# TRS-80.net
KiCad netlist of a schematic drawn in EAGLE
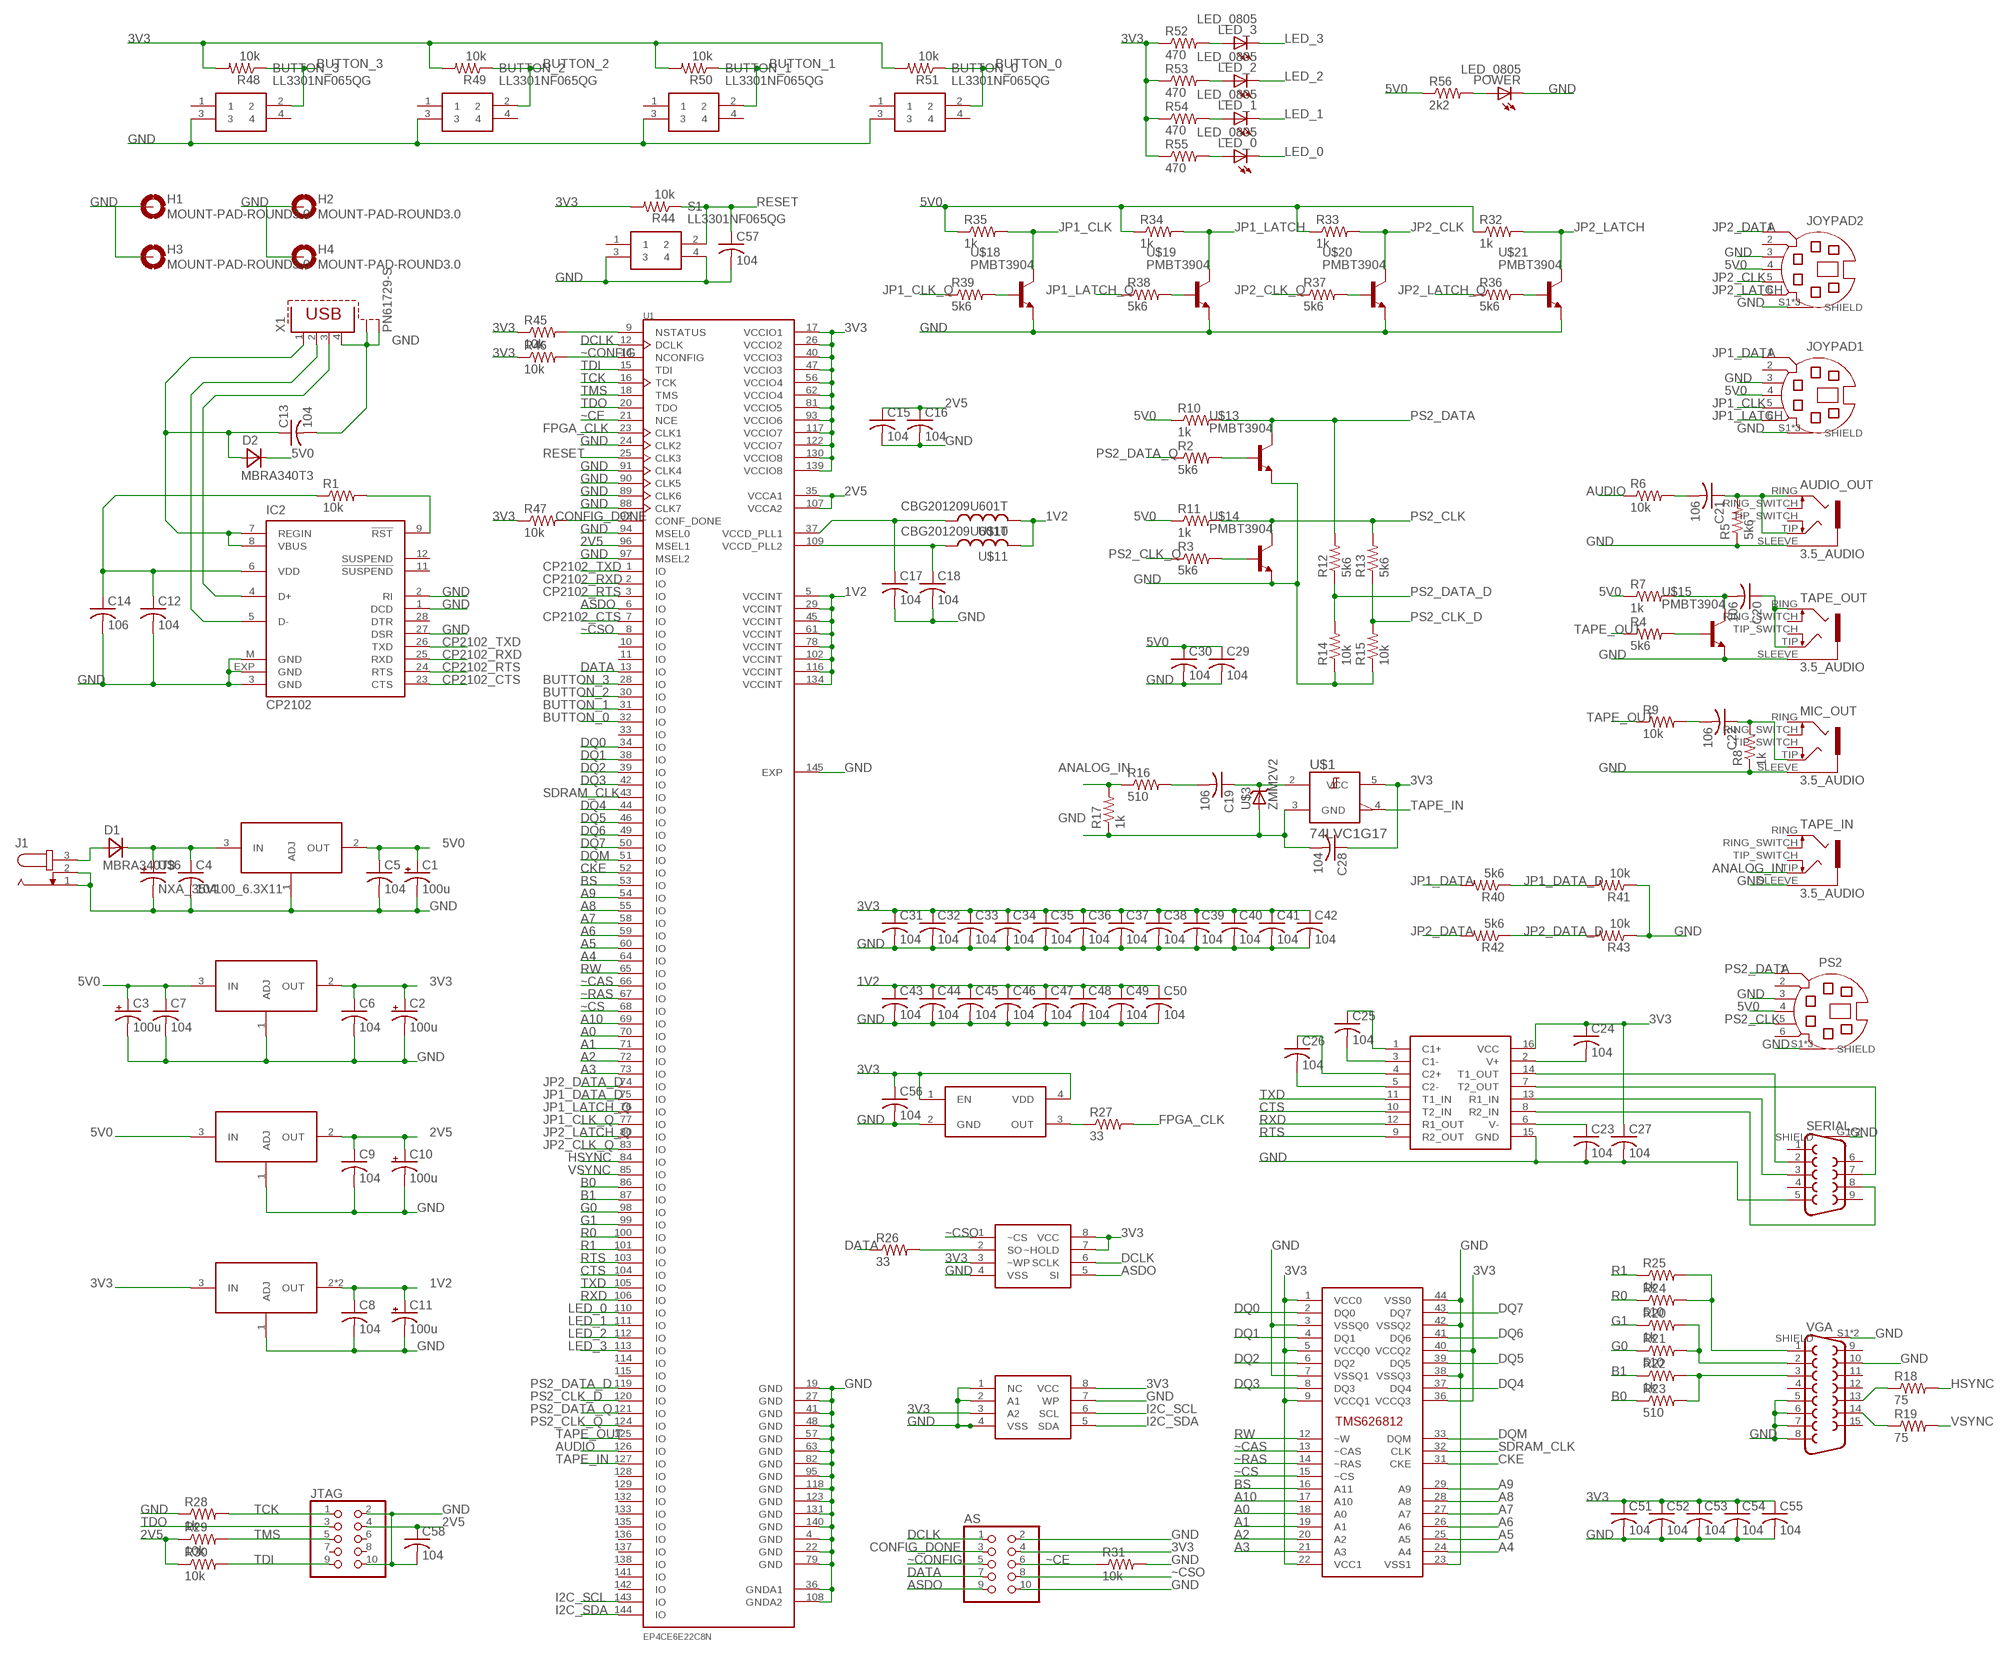
[diagram p0: schematic, sheet 1]

(export (version "E")
  (design (tool "Eeschema 10.0.6"))
  (components
    (comp (ref "AS")
      (value "PINHD-2X5")
      (footprint "eagle-import:2X05")
      (libsource (lib "eagle-import") (part "PINHD-2X5"))
    )
    (comp (ref "AUDIO_OUT")
      (value "3.5_AUDIO")
      (footprint "eagle-import:3.5_AUDIO")
      (libsource (lib "eagle-import") (part "3.5_AUDIO"))
    )
    (comp (ref "BUTTON_0")
      (value "LL3301NF065QG")
      (footprint "eagle-import:LL3301NF065QG")
      (fields (field (name "MOUSER_PART_NUMBER") "612-LL3301NF065QG"))
      (libsource (lib "eagle-import") (part "LL3301NF065QG"))
    )
    (comp (ref "BUTTON_1")
      (value "LL3301NF065QG")
      (footprint "eagle-import:LL3301NF065QG")
      (fields (field (name "MOUSER_PART_NUMBER") "612-LL3301NF065QG"))
      (libsource (lib "eagle-import") (part "LL3301NF065QG"))
    )
    (comp (ref "BUTTON_2")
      (value "LL3301NF065QG")
      (footprint "eagle-import:LL3301NF065QG")
      (fields (field (name "MOUSER_PART_NUMBER") "612-LL3301NF065QG"))
      (libsource (lib "eagle-import") (part "LL3301NF065QG"))
    )
    (comp (ref "BUTTON_3")
      (value "LL3301NF065QG")
      (footprint "eagle-import:LL3301NF065QG")
      (fields (field (name "MOUSER_PART_NUMBER") "612-LL3301NF065QG"))
      (libsource (lib "eagle-import") (part "LL3301NF065QG"))
    )
    (comp (ref "C1")
      (value "100u")
      (footprint "eagle-import:UD-6,3X5,8_NICHICON")
      (libsource (lib "eagle-import") (part "CPOL-USUD-6,3X5,8"))
    )
    (comp (ref "C2")
      (value "100u")
      (footprint "eagle-import:UD-6,3X5,8_NICHICON")
      (libsource (lib "eagle-import") (part "CPOL-USUD-6,3X5,8"))
    )
    (comp (ref "C3")
      (value "100u")
      (footprint "eagle-import:UD-6,3X5,8_NICHICON")
      (libsource (lib "eagle-import") (part "CPOL-USUD-6,3X5,8"))
    )
    (comp (ref "C4")
      (value "104")
      (footprint "eagle-import:C0805")
      (libsource (lib "eagle-import") (part "C-USC0805"))
    )
    (comp (ref "C5")
      (value "104")
      (footprint "eagle-import:C0805")
      (libsource (lib "eagle-import") (part "C-USC0805"))
    )
    (comp (ref "C6")
      (value "104")
      (footprint "eagle-import:C0805")
      (libsource (lib "eagle-import") (part "C-USC0805"))
    )
    (comp (ref "C7")
      (value "104")
      (footprint "eagle-import:C0805")
      (libsource (lib "eagle-import") (part "C-USC0805"))
    )
    (comp (ref "C8")
      (value "104")
      (footprint "eagle-import:C0805")
      (libsource (lib "eagle-import") (part "C-USC0805"))
    )
    (comp (ref "C9")
      (value "104")
      (footprint "eagle-import:C0805")
      (libsource (lib "eagle-import") (part "C-USC0805"))
    )
    (comp (ref "C10")
      (value "100u")
      (footprint "eagle-import:UD-6,3X5,8_NICHICON")
      (libsource (lib "eagle-import") (part "CPOL-USUD-6,3X5,8"))
    )
    (comp (ref "C11")
      (value "100u")
      (footprint "eagle-import:UD-6,3X5,8_NICHICON")
      (libsource (lib "eagle-import") (part "CPOL-USUD-6,3X5,8"))
    )
    (comp (ref "C12")
      (value "104")
      (footprint "eagle-import:C0805")
      (libsource (lib "eagle-import") (part "C-USC0805"))
    )
    (comp (ref "C13")
      (value "104")
      (footprint "eagle-import:C0805")
      (libsource (lib "eagle-import") (part "C-USC0805"))
    )
    (comp (ref "C14")
      (value "106")
      (footprint "eagle-import:C1206")
      (libsource (lib "eagle-import") (part "C-USC1206"))
    )
    (comp (ref "C15")
      (value "104")
      (footprint "eagle-import:C0805")
      (libsource (lib "eagle-import") (part "C-USC0805"))
    )
    (comp (ref "C16")
      (value "104")
      (footprint "eagle-import:C0805")
      (libsource (lib "eagle-import") (part "C-USC0805"))
    )
    (comp (ref "C17")
      (value "104")
      (footprint "eagle-import:C0805")
      (libsource (lib "eagle-import") (part "C-USC0805"))
    )
    (comp (ref "C18")
      (value "104")
      (footprint "eagle-import:C0805")
      (libsource (lib "eagle-import") (part "C-USC0805"))
    )
    (comp (ref "C19")
      (value "106")
      (footprint "eagle-import:C1206")
      (libsource (lib "eagle-import") (part "C-USC1206"))
    )
    (comp (ref "C20")
      (value "106")
      (footprint "eagle-import:C1206")
      (libsource (lib "eagle-import") (part "C-USC1206"))
    )
    (comp (ref "C21")
      (value "106")
      (footprint "eagle-import:C1206")
      (libsource (lib "eagle-import") (part "C-USC1206"))
    )
    (comp (ref "C22")
      (value "106")
      (footprint "eagle-import:C1206")
      (libsource (lib "eagle-import") (part "C-USC1206"))
    )
    (comp (ref "C23")
      (value "104")
      (footprint "eagle-import:C0805")
      (libsource (lib "eagle-import") (part "C-USC0805"))
    )
    (comp (ref "C24")
      (value "104")
      (footprint "eagle-import:C0805")
      (libsource (lib "eagle-import") (part "C-USC0805"))
    )
    (comp (ref "C25")
      (value "104")
      (footprint "eagle-import:C0805")
      (libsource (lib "eagle-import") (part "C-USC0805"))
    )
    (comp (ref "C26")
      (value "104")
      (footprint "eagle-import:C0805")
      (libsource (lib "eagle-import") (part "C-USC0805"))
    )
    (comp (ref "C27")
      (value "104")
      (footprint "eagle-import:C0805")
      (libsource (lib "eagle-import") (part "C-USC0805"))
    )
    (comp (ref "C28")
      (value "104")
      (footprint "eagle-import:C0805")
      (libsource (lib "eagle-import") (part "C-USC0805"))
    )
    (comp (ref "C29")
      (value "104")
      (footprint "eagle-import:C0805")
      (libsource (lib "eagle-import") (part "C-USC0805"))
    )
    (comp (ref "C30")
      (value "104")
      (footprint "eagle-import:C0805")
      (libsource (lib "eagle-import") (part "C-USC0805"))
    )
    (comp (ref "C31")
      (value "104")
      (footprint "eagle-import:C0805")
      (libsource (lib "eagle-import") (part "C-USC0805"))
    )
    (comp (ref "C32")
      (value "104")
      (footprint "eagle-import:C0805")
      (libsource (lib "eagle-import") (part "C-USC0805"))
    )
    (comp (ref "C33")
      (value "104")
      (footprint "eagle-import:C0805")
      (libsource (lib "eagle-import") (part "C-USC0805"))
    )
    (comp (ref "C34")
      (value "104")
      (footprint "eagle-import:C0805")
      (libsource (lib "eagle-import") (part "C-USC0805"))
    )
    (comp (ref "C35")
      (value "104")
      (footprint "eagle-import:C0805")
      (libsource (lib "eagle-import") (part "C-USC0805"))
    )
    (comp (ref "C36")
      (value "104")
      (footprint "eagle-import:C0805")
      (libsource (lib "eagle-import") (part "C-USC0805"))
    )
    (comp (ref "C37")
      (value "104")
      (footprint "eagle-import:C0805")
      (libsource (lib "eagle-import") (part "C-USC0805"))
    )
    (comp (ref "C38")
      (value "104")
      (footprint "eagle-import:C0805")
      (libsource (lib "eagle-import") (part "C-USC0805"))
    )
    (comp (ref "C39")
      (value "104")
      (footprint "eagle-import:C0805")
      (libsource (lib "eagle-import") (part "C-USC0805"))
    )
    (comp (ref "C40")
      (value "104")
      (footprint "eagle-import:C0805")
      (libsource (lib "eagle-import") (part "C-USC0805"))
    )
    (comp (ref "C41")
      (value "104")
      (footprint "eagle-import:C0805")
      (libsource (lib "eagle-import") (part "C-USC0805"))
    )
    (comp (ref "C42")
      (value "104")
      (footprint "eagle-import:C0805")
      (libsource (lib "eagle-import") (part "C-USC0805"))
    )
    (comp (ref "C43")
      (value "104")
      (footprint "eagle-import:C0805")
      (libsource (lib "eagle-import") (part "C-USC0805"))
    )
    (comp (ref "C44")
      (value "104")
      (footprint "eagle-import:C0805")
      (libsource (lib "eagle-import") (part "C-USC0805"))
    )
    (comp (ref "C45")
      (value "104")
      (footprint "eagle-import:C0805")
      (libsource (lib "eagle-import") (part "C-USC0805"))
    )
    (comp (ref "C46")
      (value "104")
      (footprint "eagle-import:C0805")
      (libsource (lib "eagle-import") (part "C-USC0805"))
    )
    (comp (ref "C47")
      (value "104")
      (footprint "eagle-import:C0805")
      (libsource (lib "eagle-import") (part "C-USC0805"))
    )
    (comp (ref "C48")
      (value "104")
      (footprint "eagle-import:C0805")
      (libsource (lib "eagle-import") (part "C-USC0805"))
    )
    (comp (ref "C49")
      (value "104")
      (footprint "eagle-import:C0805")
      (libsource (lib "eagle-import") (part "C-USC0805"))
    )
    (comp (ref "C50")
      (value "104")
      (footprint "eagle-import:C0805")
      (libsource (lib "eagle-import") (part "C-USC0805"))
    )
    (comp (ref "C51")
      (value "104")
      (footprint "eagle-import:C0805")
      (libsource (lib "eagle-import") (part "C-USC0805"))
    )
    (comp (ref "C52")
      (value "104")
      (footprint "eagle-import:C0805")
      (libsource (lib "eagle-import") (part "C-USC0805"))
    )
    (comp (ref "C53")
      (value "104")
      (footprint "eagle-import:C0805")
      (libsource (lib "eagle-import") (part "C-USC0805"))
    )
    (comp (ref "C54")
      (value "104")
      (footprint "eagle-import:C0805")
      (libsource (lib "eagle-import") (part "C-USC0805"))
    )
    (comp (ref "C55")
      (value "104")
      (footprint "eagle-import:C0805")
      (libsource (lib "eagle-import") (part "C-USC0805"))
    )
    (comp (ref "C56")
      (value "104")
      (footprint "eagle-import:C0805")
      (libsource (lib "eagle-import") (part "C-USC0805"))
    )
    (comp (ref "C57")
      (value "104")
      (footprint "eagle-import:C0805")
      (libsource (lib "eagle-import") (part "C-USC0805"))
    )
    (comp (ref "C58")
      (value "104")
      (footprint "eagle-import:C0805")
      (libsource (lib "eagle-import") (part "C-USC0805"))
    )
    (comp (ref "D1")
      (value "MBRA340T3")
      (footprint "eagle-import:SMA")
      (libsource (lib "eagle-import") (part "MBRA340T3"))
    )
    (comp (ref "D2")
      (value "MBRA340T3")
      (footprint "eagle-import:SMA")
      (libsource (lib "eagle-import") (part "MBRA340T3"))
    )
    (comp (ref "H1")
      (value "MOUNT-PAD-ROUND3.0")
      (footprint "eagle-import:3,0-PAD")
      (libsource (lib "eagle-import") (part "MOUNT-PAD-ROUND3.0"))
    )
    (comp (ref "H2")
      (value "MOUNT-PAD-ROUND3.0")
      (footprint "eagle-import:3,0-PAD")
      (libsource (lib "eagle-import") (part "MOUNT-PAD-ROUND3.0"))
    )
    (comp (ref "H3")
      (value "MOUNT-PAD-ROUND3.0")
      (footprint "eagle-import:3,0-PAD")
      (libsource (lib "eagle-import") (part "MOUNT-PAD-ROUND3.0"))
    )
    (comp (ref "H4")
      (value "MOUNT-PAD-ROUND3.0")
      (footprint "eagle-import:3,0-PAD")
      (libsource (lib "eagle-import") (part "MOUNT-PAD-ROUND3.0"))
    )
    (comp (ref "IC2")
      (value "CP2102")
      (footprint "eagle-import:MLP28")
      (fields (field (name "MF") "FARNELL") (field (name "MPN") "CP2102-GM"))
      (libsource (lib "eagle-import") (part "CP2102"))
    )
    (comp (ref "J1")
      (value "JACK-PLUG1")
      (footprint "eagle-import:SPC4078")
      (libsource (lib "eagle-import") (part "JACK-PLUG1"))
    )
    (comp (ref "JOYPAD1")
      (value "MD06SS")
      (footprint "eagle-import:MDIN06SS")
      (libsource (lib "eagle-import") (part "MD06SS"))
    )
    (comp (ref "JOYPAD2")
      (value "MD06SS")
      (footprint "eagle-import:MDIN06SS")
      (libsource (lib "eagle-import") (part "MD06SS"))
    )
    (comp (ref "JTAG")
      (value "PINHD-2X5")
      (footprint "eagle-import:2X05")
      (libsource (lib "eagle-import") (part "PINHD-2X5"))
    )
    (comp (ref "LED_0")
      (value "LED_0805")
      (footprint "eagle-import:CHIP-LED0805")
      (libsource (lib "eagle-import") (part "LED_0805"))
    )
    (comp (ref "LED_1")
      (value "LED_0805")
      (footprint "eagle-import:CHIP-LED0805")
      (libsource (lib "eagle-import") (part "LED_0805"))
    )
    (comp (ref "LED_2")
      (value "LED_0805")
      (footprint "eagle-import:CHIP-LED0805")
      (libsource (lib "eagle-import") (part "LED_0805"))
    )
    (comp (ref "LED_3")
      (value "LED_0805")
      (footprint "eagle-import:CHIP-LED0805")
      (libsource (lib "eagle-import") (part "LED_0805"))
    )
    (comp (ref "MIC_OUT")
      (value "3.5_AUDIO")
      (footprint "eagle-import:3.5_AUDIO")
      (libsource (lib "eagle-import") (part "3.5_AUDIO"))
    )
    (comp (ref "POWER")
      (value "LED_0805")
      (footprint "eagle-import:CHIP-LED0805")
      (libsource (lib "eagle-import") (part "LED_0805"))
    )
    (comp (ref "PS2")
      (value "MD06SS")
      (footprint "eagle-import:MDIN06SS")
      (libsource (lib "eagle-import") (part "MD06SS"))
    )
    (comp (ref "R1")
      (value "10k")
      (footprint "eagle-import:R0805")
      (libsource (lib "eagle-import") (part "R-US_R0805"))
    )
    (comp (ref "R2")
      (value "5k6")
      (footprint "eagle-import:R0805")
      (libsource (lib "eagle-import") (part "R-US_R0805"))
    )
    (comp (ref "R3")
      (value "5k6")
      (footprint "eagle-import:R0805")
      (libsource (lib "eagle-import") (part "R-US_R0805"))
    )
    (comp (ref "R4")
      (value "5k6")
      (footprint "eagle-import:R0805")
      (libsource (lib "eagle-import") (part "R-US_R0805"))
    )
    (comp (ref "R5")
      (value "5k6")
      (footprint "eagle-import:R0805")
      (libsource (lib "eagle-import") (part "R-US_R0805"))
    )
    (comp (ref "R6")
      (value "10k")
      (footprint "eagle-import:R0805")
      (libsource (lib "eagle-import") (part "R-US_R0805"))
    )
    (comp (ref "R7")
      (value "1k")
      (footprint "eagle-import:R0805")
      (libsource (lib "eagle-import") (part "R-US_R0805"))
    )
    (comp (ref "R8")
      (value "1k")
      (footprint "eagle-import:R0805")
      (libsource (lib "eagle-import") (part "R-US_R0805"))
    )
    (comp (ref "R9")
      (value "10k")
      (footprint "eagle-import:R0805")
      (libsource (lib "eagle-import") (part "R-US_R0805"))
    )
    (comp (ref "R10")
      (value "1k")
      (footprint "eagle-import:R0805")
      (libsource (lib "eagle-import") (part "R-US_R0805"))
    )
    (comp (ref "R11")
      (value "1k")
      (footprint "eagle-import:R0805")
      (libsource (lib "eagle-import") (part "R-US_R0805"))
    )
    (comp (ref "R12")
      (value "5k6")
      (footprint "eagle-import:R0805")
      (libsource (lib "eagle-import") (part "R-US_R0805"))
    )
    (comp (ref "R13")
      (value "5k6")
      (footprint "eagle-import:R0805")
      (libsource (lib "eagle-import") (part "R-US_R0805"))
    )
    (comp (ref "R14")
      (value "10k")
      (footprint "eagle-import:R0805")
      (libsource (lib "eagle-import") (part "R-US_R0805"))
    )
    (comp (ref "R15")
      (value "10k")
      (footprint "eagle-import:R0805")
      (libsource (lib "eagle-import") (part "R-US_R0805"))
    )
    (comp (ref "R16")
      (value "510")
      (footprint "eagle-import:R0805")
      (libsource (lib "eagle-import") (part "R-US_R0805"))
    )
    (comp (ref "R17")
      (value "1k")
      (footprint "eagle-import:R0805")
      (libsource (lib "eagle-import") (part "R-US_R0805"))
    )
    (comp (ref "R18")
      (value "75")
      (footprint "eagle-import:R0805")
      (libsource (lib "eagle-import") (part "R-US_R0805"))
    )
    (comp (ref "R19")
      (value "75")
      (footprint "eagle-import:R0805")
      (libsource (lib "eagle-import") (part "R-US_R0805"))
    )
    (comp (ref "R20")
      (value "1k")
      (footprint "eagle-import:R0805")
      (libsource (lib "eagle-import") (part "R-US_R0805"))
    )
    (comp (ref "R21")
      (value "510")
      (footprint "eagle-import:R0805")
      (libsource (lib "eagle-import") (part "R-US_R0805"))
    )
    (comp (ref "R22")
      (value "1k")
      (footprint "eagle-import:R0805")
      (libsource (lib "eagle-import") (part "R-US_R0805"))
    )
    (comp (ref "R23")
      (value "510")
      (footprint "eagle-import:R0805")
      (libsource (lib "eagle-import") (part "R-US_R0805"))
    )
    (comp (ref "R24")
      (value "510")
      (footprint "eagle-import:R0805")
      (libsource (lib "eagle-import") (part "R-US_R0805"))
    )
    (comp (ref "R25")
      (value "1k")
      (footprint "eagle-import:R0805")
      (libsource (lib "eagle-import") (part "R-US_R0805"))
    )
    (comp (ref "R26")
      (value "33")
      (footprint "eagle-import:R0805")
      (libsource (lib "eagle-import") (part "R-US_R0805"))
    )
    (comp (ref "R27")
      (value "33")
      (footprint "eagle-import:R0805")
      (libsource (lib "eagle-import") (part "R-US_R0805"))
    )
    (comp (ref "R28")
      (value "1k")
      (footprint "eagle-import:R0805")
      (libsource (lib "eagle-import") (part "R-US_R0805"))
    )
    (comp (ref "R29")
      (value "10k")
      (footprint "eagle-import:R0805")
      (libsource (lib "eagle-import") (part "R-US_R0805"))
    )
    (comp (ref "R30")
      (value "10k")
      (footprint "eagle-import:R0805")
      (libsource (lib "eagle-import") (part "R-US_R0805"))
    )
    (comp (ref "R31")
      (value "10k")
      (footprint "eagle-import:R0805")
      (libsource (lib "eagle-import") (part "R-US_R0805"))
    )
    (comp (ref "R32")
      (value "1k")
      (footprint "eagle-import:R0805")
      (libsource (lib "eagle-import") (part "R-US_R0805"))
    )
    (comp (ref "R33")
      (value "1k")
      (footprint "eagle-import:R0805")
      (libsource (lib "eagle-import") (part "R-US_R0805"))
    )
    (comp (ref "R34")
      (value "1k")
      (footprint "eagle-import:R0805")
      (libsource (lib "eagle-import") (part "R-US_R0805"))
    )
    (comp (ref "R35")
      (value "1k")
      (footprint "eagle-import:R0805")
      (libsource (lib "eagle-import") (part "R-US_R0805"))
    )
    (comp (ref "R36")
      (value "5k6")
      (footprint "eagle-import:R0805")
      (libsource (lib "eagle-import") (part "R-US_R0805"))
    )
    (comp (ref "R37")
      (value "5k6")
      (footprint "eagle-import:R0805")
      (libsource (lib "eagle-import") (part "R-US_R0805"))
    )
    (comp (ref "R38")
      (value "5k6")
      (footprint "eagle-import:R0805")
      (libsource (lib "eagle-import") (part "R-US_R0805"))
    )
    (comp (ref "R39")
      (value "5k6")
      (footprint "eagle-import:R0805")
      (libsource (lib "eagle-import") (part "R-US_R0805"))
    )
    (comp (ref "R40")
      (value "5k6")
      (footprint "eagle-import:R0805")
      (libsource (lib "eagle-import") (part "R-US_R0805"))
    )
    (comp (ref "R41")
      (value "10k")
      (footprint "eagle-import:R0805")
      (libsource (lib "eagle-import") (part "R-US_R0805"))
    )
    (comp (ref "R42")
      (value "5k6")
      (footprint "eagle-import:R0805")
      (libsource (lib "eagle-import") (part "R-US_R0805"))
    )
    (comp (ref "R43")
      (value "10k")
      (footprint "eagle-import:R0805")
      (libsource (lib "eagle-import") (part "R-US_R0805"))
    )
    (comp (ref "R44")
      (value "10k")
      (footprint "eagle-import:R0805")
      (libsource (lib "eagle-import") (part "R-US_R0805"))
    )
    (comp (ref "R45")
      (value "10k")
      (footprint "eagle-import:R0805")
      (libsource (lib "eagle-import") (part "R-US_R0805"))
    )
    (comp (ref "R46")
      (value "10k")
      (footprint "eagle-import:R0805")
      (libsource (lib "eagle-import") (part "R-US_R0805"))
    )
    (comp (ref "R47")
      (value "10k")
      (footprint "eagle-import:R0805")
      (libsource (lib "eagle-import") (part "R-US_R0805"))
    )
    (comp (ref "R48")
      (value "10k")
      (footprint "eagle-import:R0805")
      (libsource (lib "eagle-import") (part "R-US_R0805"))
    )
    (comp (ref "R49")
      (value "10k")
      (footprint "eagle-import:R0805")
      (libsource (lib "eagle-import") (part "R-US_R0805"))
    )
    (comp (ref "R50")
      (value "10k")
      (footprint "eagle-import:R0805")
      (libsource (lib "eagle-import") (part "R-US_R0805"))
    )
    (comp (ref "R51")
      (value "10k")
      (footprint "eagle-import:R0805")
      (libsource (lib "eagle-import") (part "R-US_R0805"))
    )
    (comp (ref "R52")
      (value "470")
      (footprint "eagle-import:R0805")
      (libsource (lib "eagle-import") (part "R-US_R0805"))
    )
    (comp (ref "R53")
      (value "470")
      (footprint "eagle-import:R0805")
      (libsource (lib "eagle-import") (part "R-US_R0805"))
    )
    (comp (ref "R54")
      (value "470")
      (footprint "eagle-import:R0805")
      (libsource (lib "eagle-import") (part "R-US_R0805"))
    )
    (comp (ref "R55")
      (value "470")
      (footprint "eagle-import:R0805")
      (libsource (lib "eagle-import") (part "R-US_R0805"))
    )
    (comp (ref "R56")
      (value "2k2")
      (footprint "eagle-import:R0805")
      (libsource (lib "eagle-import") (part "R-US_R0805"))
    )
    (comp (ref "S1")
      (value "LL3301NF065QG")
      (footprint "eagle-import:LL3301NF065QG")
      (fields (field (name "MOUSER_PART_NUMBER") "612-LL3301NF065QG"))
      (libsource (lib "eagle-import") (part "LL3301NF065QG"))
    )
    (comp (ref "SERIAL")
      (value "F09HP")
      (footprint "eagle-import:F09HP")
      (libsource (lib "eagle-import") (part "F09HP"))
    )
    (comp (ref "TAPE_IN")
      (value "3.5_AUDIO")
      (footprint "eagle-import:3.5_AUDIO")
      (libsource (lib "eagle-import") (part "3.5_AUDIO"))
    )
    (comp (ref "TAPE_OUT")
      (value "3.5_AUDIO")
      (footprint "eagle-import:3.5_AUDIO")
      (libsource (lib "eagle-import") (part "3.5_AUDIO"))
    )
    (comp (ref "U$1")
      (value "74LVC1G17")
      (footprint "eagle-import:SOT353")
      (libsource (lib "eagle-import") (part "74LVC1G17"))
    )
    (comp (ref "U$2")
      (value "TMS626812")
      (footprint "eagle-import:TSOP44-II")
      (libsource (lib "eagle-import") (part "TMS626812"))
    )
    (comp (ref "U$3")
      (value "ZMM2V2")
      (footprint "eagle-import:SOD80C")
      (libsource (lib "eagle-import") (part "ZMM2V2"))
    )
    (comp (ref "U$4")
      (value "SP232")
      (footprint "eagle-import:SOP16")
      (libsource (lib "eagle-import") (part "SP232"))
    )
    (comp (ref "U$5")
      (value "LM1086")
      (footprint "eagle-import:D2PACK")
      (libsource (lib "eagle-import") (part "LM1086"))
    )
    (comp (ref "U$6")
      (value "NXA_35V100_6.3X11")
      (footprint "eagle-import:NXA_35V100_6.3X11")
      (libsource (lib "eagle-import") (part "NXA_35V100_6.3X11"))
    )
    (comp (ref "U$7")
      (value "LD1117D-3.3")
      (footprint "eagle-import:TO252")
      (libsource (lib "eagle-import") (part "LD1117D-3.3"))
    )
    (comp (ref "U$8")
      (value "KIA1117-2.5")
      (footprint "eagle-import:SOT223")
      (libsource (lib "eagle-import") (part "KIA1117-2.5"))
    )
    (comp (ref "U$9")
      (value "AZ1117H-1.2TRG1")
      (footprint "eagle-import:SOT223")
      (libsource (lib "eagle-import") (part "AZ1117H-1.2TRG1"))
    )
    (comp (ref "U$10")
      (value "CBG201209U601T")
      (footprint "eagle-import:C0805")
      (libsource (lib "eagle-import") (part "CBG201209U601T"))
    )
    (comp (ref "U$11")
      (value "CBG201209U601T")
      (footprint "eagle-import:C0805")
      (libsource (lib "eagle-import") (part "CBG201209U601T"))
    )
    (comp (ref "U$12")
      (value "OT705050MJBA4SL")
      (footprint "eagle-import:ASV32000MHZET")
      (libsource (lib "eagle-import") (part "OT705050MJBA4SL"))
    )
    (comp (ref "U$13")
      (value "PMBT3904")
      (footprint "eagle-import:SOT23")
      (libsource (lib "eagle-import") (part "PMBT3904"))
    )
    (comp (ref "U$14")
      (value "PMBT3904")
      (footprint "eagle-import:SOT23")
      (libsource (lib "eagle-import") (part "PMBT3904"))
    )
    (comp (ref "U$15")
      (value "PMBT3904")
      (footprint "eagle-import:SOT23")
      (libsource (lib "eagle-import") (part "PMBT3904"))
    )
    (comp (ref "U$16")
      (value "BY25Q16BS")
      (footprint "eagle-import:SO08")
      (libsource (lib "eagle-import") (part "BY25Q16BS"))
    )
    (comp (ref "U$17")
      (value "CAT24M01WI-GT3")
      (footprint "eagle-import:SO08")
      (libsource (lib "eagle-import") (part "CAT24M01WI-GT3"))
    )
    (comp (ref "U$18")
      (value "PMBT3904")
      (footprint "eagle-import:SOT23")
      (libsource (lib "eagle-import") (part "PMBT3904"))
    )
    (comp (ref "U$19")
      (value "PMBT3904")
      (footprint "eagle-import:SOT23")
      (libsource (lib "eagle-import") (part "PMBT3904"))
    )
    (comp (ref "U$20")
      (value "PMBT3904")
      (footprint "eagle-import:SOT23")
      (libsource (lib "eagle-import") (part "PMBT3904"))
    )
    (comp (ref "U$21")
      (value "PMBT3904")
      (footprint "eagle-import:SOT23")
      (libsource (lib "eagle-import") (part "PMBT3904"))
    )
    (comp (ref "U1")
      (value "EP4CE6E22C8N")
      (footprint "eagle-import:QFP50P2200X2200X165-145N")
      (fields (field (name "MF") "Intel"))
      (libsource (lib "eagle-import") (part "EP4CE6E22C8N"))
    )
    (comp (ref "VGA")
      (value "F15HDH")
      (footprint "eagle-import:HDF15H")
      (libsource (lib "eagle-import") (part "F15HDH"))
    )
    (comp (ref "X1")
      (value "PN61729-S")
      (footprint "eagle-import:PN61729-S")
      (libsource (lib "eagle-import") (part "PN61729-S"))
    )
  )
  (nets
    (net (code "1") (name "/1V2") (class "Default")
      (node (ref "C11") (pin "+") (pinfunction "+_+") (pintype "passive"))
      (node (ref "C43") (pin "1") (pinfunction "1_1") (pintype "passive"))
      (node (ref "C44") (pin "1") (pinfunction "1_1") (pintype "passive"))
      (node (ref "C45") (pin "1") (pinfunction "1_1") (pintype "passive"))
      (node (ref "C46") (pin "1") (pinfunction "1_1") (pintype "passive"))
      (node (ref "C47") (pin "1") (pinfunction "1_1") (pintype "passive"))
      (node (ref "C48") (pin "1") (pinfunction "1_1") (pintype "passive"))
      (node (ref "C49") (pin "1") (pinfunction "1_1") (pintype "passive"))
      (node (ref "C50") (pin "1") (pinfunction "1_1") (pintype "passive"))
      (node (ref "C8") (pin "1") (pinfunction "1_1") (pintype "passive"))
      (node (ref "U$10") (pin "2") (pinfunction "2_2") (pintype "passive"))
      (node (ref "U$11") (pin "2") (pinfunction "2_2") (pintype "passive"))
      (node (ref "U$9") (pin "2") (pinfunction "OUT_2") (pintype "bidirectional"))
      (node (ref "U$9") (pin "4") (pinfunction "OUT_4") (pintype "bidirectional"))
      (node (ref "U1") (pin "102") (pinfunction "VCCINT_102") (pintype "power_in"))
      (node (ref "U1") (pin "116") (pinfunction "VCCINT_116") (pintype "power_in"))
      (node (ref "U1") (pin "134") (pinfunction "VCCINT_134") (pintype "power_in"))
      (node (ref "U1") (pin "29") (pinfunction "VCCINT_29") (pintype "power_in"))
      (node (ref "U1") (pin "45") (pinfunction "VCCINT_45") (pintype "power_in"))
      (node (ref "U1") (pin "5") (pinfunction "VCCINT_5") (pintype "power_in"))
      (node (ref "U1") (pin "61") (pinfunction "VCCINT_61") (pintype "power_in"))
      (node (ref "U1") (pin "78") (pinfunction "VCCINT_78") (pintype "power_in"))
    )
    (net (code "2") (name "/2V5") (class "Default")
      (node (ref "C10") (pin "+") (pinfunction "+_+") (pintype "passive"))
      (node (ref "C15") (pin "1") (pinfunction "1_1") (pintype "passive"))
      (node (ref "C16") (pin "1") (pinfunction "1_1") (pintype "passive"))
      (node (ref "C58") (pin "1") (pinfunction "1_1") (pintype "passive"))
      (node (ref "C9") (pin "1") (pinfunction "1_1") (pintype "passive"))
      (node (ref "JTAG") (pin "4") (pinfunction "4_4") (pintype "passive"))
      (node (ref "R29") (pin "1") (pinfunction "1_1") (pintype "passive"))
      (node (ref "R30") (pin "1") (pinfunction "1_1") (pintype "passive"))
      (node (ref "U$8") (pin "2") (pinfunction "OUT_2") (pintype "bidirectional"))
      (node (ref "U1") (pin "107") (pinfunction "VCCA2_107") (pintype "power_in"))
      (node (ref "U1") (pin "35") (pinfunction "VCCA1_35") (pintype "power_in"))
      (node (ref "U1") (pin "96") (pinfunction "MSEL1_96") (pintype "bidirectional"))
    )
    (net (code "3") (name "/3V3") (class "Default")
      (node (ref "AS") (pin "4") (pinfunction "4_4") (pintype "passive"))
      (node (ref "C2") (pin "+") (pinfunction "+_+") (pintype "passive"))
      (node (ref "C24") (pin "1") (pinfunction "1_1") (pintype "passive"))
      (node (ref "C27") (pin "1") (pinfunction "1_1") (pintype "passive"))
      (node (ref "C28") (pin "1") (pinfunction "1_1") (pintype "passive"))
      (node (ref "C31") (pin "1") (pinfunction "1_1") (pintype "passive"))
      (node (ref "C32") (pin "1") (pinfunction "1_1") (pintype "passive"))
      (node (ref "C33") (pin "1") (pinfunction "1_1") (pintype "passive"))
      (node (ref "C34") (pin "1") (pinfunction "1_1") (pintype "passive"))
      (node (ref "C35") (pin "1") (pinfunction "1_1") (pintype "passive"))
      (node (ref "C36") (pin "1") (pinfunction "1_1") (pintype "passive"))
      (node (ref "C37") (pin "1") (pinfunction "1_1") (pintype "passive"))
      (node (ref "C38") (pin "1") (pinfunction "1_1") (pintype "passive"))
      (node (ref "C39") (pin "1") (pinfunction "1_1") (pintype "passive"))
      (node (ref "C40") (pin "1") (pinfunction "1_1") (pintype "passive"))
      (node (ref "C41") (pin "1") (pinfunction "1_1") (pintype "passive"))
      (node (ref "C42") (pin "1") (pinfunction "1_1") (pintype "passive"))
      (node (ref "C51") (pin "1") (pinfunction "1_1") (pintype "passive"))
      (node (ref "C52") (pin "1") (pinfunction "1_1") (pintype "passive"))
      (node (ref "C53") (pin "1") (pinfunction "1_1") (pintype "passive"))
      (node (ref "C54") (pin "1") (pinfunction "1_1") (pintype "passive"))
      (node (ref "C55") (pin "1") (pinfunction "1_1") (pintype "passive"))
      (node (ref "C56") (pin "1") (pinfunction "1_1") (pintype "passive"))
      (node (ref "C6") (pin "1") (pinfunction "1_1") (pintype "passive"))
      (node (ref "R44") (pin "2") (pinfunction "2_2") (pintype "passive"))
      (node (ref "R45") (pin "1") (pinfunction "1_1") (pintype "passive"))
      (node (ref "R46") (pin "1") (pinfunction "1_1") (pintype "passive"))
      (node (ref "R47") (pin "1") (pinfunction "1_1") (pintype "passive"))
      (node (ref "R48") (pin "2") (pinfunction "2_2") (pintype "passive"))
      (node (ref "R49") (pin "2") (pinfunction "2_2") (pintype "passive"))
      (node (ref "R50") (pin "2") (pinfunction "2_2") (pintype "passive"))
      (node (ref "R51") (pin "2") (pinfunction "2_2") (pintype "passive"))
      (node (ref "R52") (pin "1") (pinfunction "1_1") (pintype "passive"))
      (node (ref "R53") (pin "1") (pinfunction "1_1") (pintype "passive"))
      (node (ref "R54") (pin "1") (pinfunction "1_1") (pintype "passive"))
      (node (ref "R55") (pin "1") (pinfunction "1_1") (pintype "passive"))
      (node (ref "U$1") (pin "5") (pinfunction "VCC_5") (pintype "power_in"))
      (node (ref "U$12") (pin "1") (pinfunction "EN_1") (pintype "bidirectional"))
      (node (ref "U$12") (pin "4") (pinfunction "VDD_4") (pintype "bidirectional"))
      (node (ref "U$16") (pin "3") (pinfunction "~{WP}_3") (pintype "bidirectional"))
      (node (ref "U$16") (pin "7") (pinfunction "~{HOLD}_7") (pintype "bidirectional"))
      (node (ref "U$16") (pin "8") (pinfunction "VCC_8") (pintype "bidirectional"))
      (node (ref "U$17") (pin "3") (pinfunction "A2_3") (pintype "bidirectional"))
      (node (ref "U$17") (pin "8") (pinfunction "VCC_8") (pintype "bidirectional"))
      (node (ref "U$2") (pin "1") (pinfunction "VCC0_1") (pintype "bidirectional"))
      (node (ref "U$2") (pin "22") (pinfunction "VCC1_22") (pintype "bidirectional"))
      (node (ref "U$2") (pin "36") (pinfunction "VCCQ3_36") (pintype "bidirectional"))
      (node (ref "U$2") (pin "40") (pinfunction "VCCQ2_40") (pintype "bidirectional"))
      (node (ref "U$2") (pin "5") (pinfunction "VCCQ0_5") (pintype "bidirectional"))
      (node (ref "U$2") (pin "9") (pinfunction "VCCQ1_9") (pintype "bidirectional"))
      (node (ref "U$4") (pin "16") (pinfunction "VCC_16") (pintype "bidirectional"))
      (node (ref "U$7") (pin "2") (pinfunction "OUT_2") (pintype "bidirectional"))
      (node (ref "U$9") (pin "3") (pinfunction "IN_3") (pintype "bidirectional"))
      (node (ref "U1") (pin "117") (pinfunction "VCCIO7_117") (pintype "power_in"))
      (node (ref "U1") (pin "122") (pinfunction "VCCIO7_122") (pintype "power_in"))
      (node (ref "U1") (pin "130") (pinfunction "VCCIO8_130") (pintype "power_in"))
      (node (ref "U1") (pin "139") (pinfunction "VCCIO8_139") (pintype "power_in"))
      (node (ref "U1") (pin "17") (pinfunction "VCCIO1_17") (pintype "power_in"))
      (node (ref "U1") (pin "26") (pinfunction "VCCIO2_26") (pintype "power_in"))
      (node (ref "U1") (pin "40") (pinfunction "VCCIO3_40") (pintype "power_in"))
      (node (ref "U1") (pin "47") (pinfunction "VCCIO3_47") (pintype "power_in"))
      (node (ref "U1") (pin "56") (pinfunction "VCCIO4_56") (pintype "power_in"))
      (node (ref "U1") (pin "62") (pinfunction "VCCIO4_62") (pintype "power_in"))
      (node (ref "U1") (pin "81") (pinfunction "VCCIO5_81") (pintype "power_in"))
      (node (ref "U1") (pin "93") (pinfunction "VCCIO6_93") (pintype "power_in"))
    )
    (net (code "4") (name "/5V0") (class "Default")
      (node (ref "C1") (pin "+") (pinfunction "+_+") (pintype "passive"))
      (node (ref "C29") (pin "1") (pinfunction "1_1") (pintype "passive"))
      (node (ref "C3") (pin "+") (pinfunction "+_+") (pintype "passive"))
      (node (ref "C30") (pin "1") (pinfunction "1_1") (pintype "passive"))
      (node (ref "C5") (pin "1") (pinfunction "1_1") (pintype "passive"))
      (node (ref "C7") (pin "1") (pinfunction "1_1") (pintype "passive"))
      (node (ref "D2") (pin "C") (pinfunction "C_C") (pintype "passive"))
      (node (ref "JOYPAD1") (pin "4") (pinfunction "4_4") (pintype "passive"))
      (node (ref "JOYPAD2") (pin "4") (pinfunction "4_4") (pintype "passive"))
      (node (ref "PS2") (pin "4") (pinfunction "4_4") (pintype "passive"))
      (node (ref "R10") (pin "1") (pinfunction "1_1") (pintype "passive"))
      (node (ref "R11") (pin "1") (pinfunction "1_1") (pintype "passive"))
      (node (ref "R32") (pin "1") (pinfunction "1_1") (pintype "passive"))
      (node (ref "R33") (pin "1") (pinfunction "1_1") (pintype "passive"))
      (node (ref "R34") (pin "1") (pinfunction "1_1") (pintype "passive"))
      (node (ref "R35") (pin "1") (pinfunction "1_1") (pintype "passive"))
      (node (ref "R56") (pin "1") (pinfunction "1_1") (pintype "passive"))
      (node (ref "R7") (pin "1") (pinfunction "1_1") (pintype "passive"))
      (node (ref "U$5") (pin "2") (pinfunction "OUT_2") (pintype "bidirectional"))
      (node (ref "U$7") (pin "3") (pinfunction "IN_3") (pintype "bidirectional"))
      (node (ref "U$8") (pin "3") (pinfunction "IN_3") (pintype "bidirectional"))
    )
    (net (code "5") (name "/A0") (class "Default")
      (node (ref "U$2") (pin "18") (pinfunction "A0_18") (pintype "bidirectional"))
      (node (ref "U1") (pin "70") (pinfunction "IO_70") (pintype "bidirectional"))
    )
    (net (code "6") (name "/A1") (class "Default")
      (node (ref "U$2") (pin "19") (pinfunction "A1_19") (pintype "bidirectional"))
      (node (ref "U1") (pin "71") (pinfunction "IO_71") (pintype "bidirectional"))
    )
    (net (code "7") (name "/A2") (class "Default")
      (node (ref "U$2") (pin "20") (pinfunction "A2_20") (pintype "bidirectional"))
      (node (ref "U1") (pin "72") (pinfunction "IO_72") (pintype "bidirectional"))
    )
    (net (code "8") (name "/A3") (class "Default")
      (node (ref "U$2") (pin "21") (pinfunction "A3_21") (pintype "bidirectional"))
      (node (ref "U1") (pin "73") (pinfunction "IO_73") (pintype "bidirectional"))
    )
    (net (code "9") (name "/A4") (class "Default")
      (node (ref "U$2") (pin "24") (pinfunction "A4_24") (pintype "bidirectional"))
      (node (ref "U1") (pin "64") (pinfunction "IO_64") (pintype "bidirectional"))
    )
    (net (code "10") (name "/A5") (class "Default")
      (node (ref "U$2") (pin "25") (pinfunction "A5_25") (pintype "bidirectional"))
      (node (ref "U1") (pin "60") (pinfunction "IO_60") (pintype "bidirectional"))
    )
    (net (code "11") (name "/A6") (class "Default")
      (node (ref "U$2") (pin "26") (pinfunction "A6_26") (pintype "bidirectional"))
      (node (ref "U1") (pin "59") (pinfunction "IO_59") (pintype "bidirectional"))
    )
    (net (code "12") (name "/A7") (class "Default")
      (node (ref "U$2") (pin "27") (pinfunction "A7_27") (pintype "bidirectional"))
      (node (ref "U1") (pin "58") (pinfunction "IO_58") (pintype "bidirectional"))
    )
    (net (code "13") (name "/A8") (class "Default")
      (node (ref "U$2") (pin "28") (pinfunction "A8_28") (pintype "bidirectional"))
      (node (ref "U1") (pin "55") (pinfunction "IO_55") (pintype "bidirectional"))
    )
    (net (code "14") (name "/A9") (class "Default")
      (node (ref "U$2") (pin "29") (pinfunction "A9_29") (pintype "bidirectional"))
      (node (ref "U1") (pin "54") (pinfunction "IO_54") (pintype "bidirectional"))
    )
    (net (code "15") (name "/A10") (class "Default")
      (node (ref "U$2") (pin "17") (pinfunction "A10_17") (pintype "bidirectional"))
      (node (ref "U1") (pin "69") (pinfunction "IO_69") (pintype "bidirectional"))
    )
    (net (code "16") (name "/ANALOG_IN") (class "Default")
      (node (ref "R16") (pin "1") (pinfunction "1_1") (pintype "passive"))
      (node (ref "R17") (pin "2") (pinfunction "2_2") (pintype "passive"))
      (node (ref "TAPE_IN") (pin "TIP") (pinfunction "TIP_TIP") (pintype "passive"))
    )
    (net (code "17") (name "/ASDO") (class "Default")
      (node (ref "AS") (pin "9") (pinfunction "9_9") (pintype "passive"))
      (node (ref "U$16") (pin "5") (pinfunction "SI_5") (pintype "bidirectional"))
      (node (ref "U1") (pin "6") (pinfunction "IO_6") (pintype "bidirectional"))
    )
    (net (code "18") (name "/AUDIO") (class "Default")
      (node (ref "R6") (pin "1") (pinfunction "1_1") (pintype "passive"))
      (node (ref "U1") (pin "126") (pinfunction "IO_126") (pintype "bidirectional"))
    )
    (net (code "19") (name "/B0") (class "Default")
      (node (ref "R23") (pin "1") (pinfunction "1_1") (pintype "passive"))
      (node (ref "U1") (pin "86") (pinfunction "IO_86") (pintype "bidirectional"))
    )
    (net (code "20") (name "/B1") (class "Default")
      (node (ref "R22") (pin "1") (pinfunction "1_1") (pintype "passive"))
      (node (ref "U1") (pin "87") (pinfunction "IO_87") (pintype "bidirectional"))
    )
    (net (code "21") (name "/BS") (class "Default")
      (node (ref "U$2") (pin "16") (pinfunction "A11_16") (pintype "bidirectional"))
      (node (ref "U1") (pin "53") (pinfunction "IO_53") (pintype "bidirectional"))
    )
    (net (code "22") (name "/BUTTON_0") (class "Default")
      (node (ref "BUTTON_0") (pin "2") (pinfunction "2_2") (pintype "bidirectional"))
      (node (ref "R51") (pin "1") (pinfunction "1_1") (pintype "passive"))
      (node (ref "U1") (pin "32") (pinfunction "IO_32") (pintype "bidirectional"))
    )
    (net (code "23") (name "/BUTTON_1") (class "Default")
      (node (ref "BUTTON_1") (pin "2") (pinfunction "2_2") (pintype "bidirectional"))
      (node (ref "R50") (pin "1") (pinfunction "1_1") (pintype "passive"))
      (node (ref "U1") (pin "31") (pinfunction "IO_31") (pintype "bidirectional"))
    )
    (net (code "24") (name "/BUTTON_2") (class "Default")
      (node (ref "BUTTON_2") (pin "2") (pinfunction "2_2") (pintype "bidirectional"))
      (node (ref "R49") (pin "1") (pinfunction "1_1") (pintype "passive"))
      (node (ref "U1") (pin "30") (pinfunction "IO_30") (pintype "bidirectional"))
    )
    (net (code "25") (name "/BUTTON_3") (class "Default")
      (node (ref "BUTTON_3") (pin "2") (pinfunction "2_2") (pintype "bidirectional"))
      (node (ref "R48") (pin "1") (pinfunction "1_1") (pintype "passive"))
      (node (ref "U1") (pin "28") (pinfunction "IO_28") (pintype "bidirectional"))
    )
    (net (code "26") (name "/CKE") (class "Default")
      (node (ref "U$2") (pin "31") (pinfunction "CKE_31") (pintype "bidirectional"))
      (node (ref "U1") (pin "52") (pinfunction "IO_52") (pintype "bidirectional"))
    )
    (net (code "27") (name "/CONFIG_DONE") (class "Default")
      (node (ref "AS") (pin "3") (pinfunction "3_3") (pintype "passive"))
      (node (ref "R47") (pin "2") (pinfunction "2_2") (pintype "passive"))
      (node (ref "U1") (pin "92") (pinfunction "CONF_DONE_92") (pintype "bidirectional"))
    )
    (net (code "28") (name "/CP2102_CTS") (class "Default")
      (node (ref "IC2") (pin "23") (pinfunction "CTS_23") (pintype "input"))
      (node (ref "U1") (pin "7") (pinfunction "IO_7") (pintype "bidirectional"))
    )
    (net (code "29") (name "/CP2102_RTS") (class "Default")
      (node (ref "IC2") (pin "24") (pinfunction "RTS_24") (pintype "output"))
      (node (ref "U1") (pin "3") (pinfunction "IO_3") (pintype "bidirectional"))
    )
    (net (code "30") (name "/CP2102_RXD") (class "Default")
      (node (ref "IC2") (pin "25") (pinfunction "RXD_25") (pintype "input"))
      (node (ref "U1") (pin "2") (pinfunction "IO_2") (pintype "bidirectional"))
    )
    (net (code "31") (name "/CP2102_TXD") (class "Default")
      (node (ref "IC2") (pin "26") (pinfunction "TXD_26") (pintype "output"))
      (node (ref "U1") (pin "1") (pinfunction "IO_1") (pintype "bidirectional"))
    )
    (net (code "32") (name "/CTS") (class "Default")
      (node (ref "U$4") (pin "10") (pinfunction "T2_IN_10") (pintype "bidirectional"))
      (node (ref "U1") (pin "104") (pinfunction "IO_104") (pintype "bidirectional"))
    )
    (net (code "33") (name "/DATA") (class "Default")
      (node (ref "AS") (pin "7") (pinfunction "7_7") (pintype "passive"))
      (node (ref "R26") (pin "1") (pinfunction "1_1") (pintype "passive"))
      (node (ref "U1") (pin "13") (pinfunction "IO_13") (pintype "bidirectional"))
    )
    (net (code "34") (name "/DCLK") (class "Default")
      (node (ref "AS") (pin "1") (pinfunction "1_1") (pintype "passive"))
      (node (ref "U$16") (pin "6") (pinfunction "SCLK_6") (pintype "bidirectional"))
      (node (ref "U1") (pin "12") (pinfunction "DCLK_12") (pintype "bidirectional"))
    )
    (net (code "35") (name "/DQ0") (class "Default")
      (node (ref "U$2") (pin "2") (pinfunction "DQ0_2") (pintype "bidirectional"))
      (node (ref "U1") (pin "34") (pinfunction "IO_34") (pintype "bidirectional"))
    )
    (net (code "36") (name "/DQ1") (class "Default")
      (node (ref "U$2") (pin "4") (pinfunction "DQ1_4") (pintype "bidirectional"))
      (node (ref "U1") (pin "38") (pinfunction "IO_38") (pintype "bidirectional"))
    )
    (net (code "37") (name "/DQ2") (class "Default")
      (node (ref "U$2") (pin "6") (pinfunction "DQ2_6") (pintype "bidirectional"))
      (node (ref "U1") (pin "39") (pinfunction "IO_39") (pintype "bidirectional"))
    )
    (net (code "38") (name "/DQ3") (class "Default")
      (node (ref "U$2") (pin "8") (pinfunction "DQ3_8") (pintype "bidirectional"))
      (node (ref "U1") (pin "42") (pinfunction "IO_42") (pintype "bidirectional"))
    )
    (net (code "39") (name "/DQ4") (class "Default")
      (node (ref "U$2") (pin "37") (pinfunction "DQ4_37") (pintype "bidirectional"))
      (node (ref "U1") (pin "44") (pinfunction "IO_44") (pintype "bidirectional"))
    )
    (net (code "40") (name "/DQ5") (class "Default")
      (node (ref "U$2") (pin "39") (pinfunction "DQ5_39") (pintype "bidirectional"))
      (node (ref "U1") (pin "46") (pinfunction "IO_46") (pintype "bidirectional"))
    )
    (net (code "41") (name "/DQ6") (class "Default")
      (node (ref "U$2") (pin "41") (pinfunction "DQ6_41") (pintype "bidirectional"))
      (node (ref "U1") (pin "49") (pinfunction "IO_49") (pintype "bidirectional"))
    )
    (net (code "42") (name "/DQ7") (class "Default")
      (node (ref "U$2") (pin "43") (pinfunction "DQ7_43") (pintype "bidirectional"))
      (node (ref "U1") (pin "50") (pinfunction "IO_50") (pintype "bidirectional"))
    )
    (net (code "43") (name "/DQM") (class "Default")
      (node (ref "U$2") (pin "33") (pinfunction "DQM_33") (pintype "bidirectional"))
      (node (ref "U1") (pin "51") (pinfunction "IO_51") (pintype "bidirectional"))
    )
    (net (code "44") (name "/FPGA_CLK") (class "Default")
      (node (ref "R27") (pin "2") (pinfunction "2_2") (pintype "passive"))
      (node (ref "U1") (pin "23") (pinfunction "CLK1_23") (pintype "bidirectional"))
    )
    (net (code "45") (name "/G0") (class "Default")
      (node (ref "R21") (pin "1") (pinfunction "1_1") (pintype "passive"))
      (node (ref "U1") (pin "98") (pinfunction "IO_98") (pintype "bidirectional"))
    )
    (net (code "46") (name "/G1") (class "Default")
      (node (ref "R20") (pin "1") (pinfunction "1_1") (pintype "passive"))
      (node (ref "U1") (pin "99") (pinfunction "IO_99") (pintype "bidirectional"))
    )
    (net (code "47") (name "/GND") (class "Default")
      (node (ref "AS") (pin "10") (pinfunction "10_10") (pintype "passive"))
      (node (ref "AS") (pin "2") (pinfunction "2_2") (pintype "passive"))
      (node (ref "AUDIO_OUT") (pin "SLEEVE") (pinfunction "SLEEVE_SLEEVE") (pintype "passive"))
      (node (ref "BUTTON_0") (pin "3") (pinfunction "3_3") (pintype "bidirectional"))
      (node (ref "BUTTON_1") (pin "3") (pinfunction "3_3") (pintype "bidirectional"))
      (node (ref "BUTTON_2") (pin "3") (pinfunction "3_3") (pintype "bidirectional"))
      (node (ref "BUTTON_3") (pin "3") (pinfunction "3_3") (pintype "bidirectional"))
      (node (ref "C1") (pin "-") (pinfunction "-_-") (pintype "passive"))
      (node (ref "C10") (pin "-") (pinfunction "-_-") (pintype "passive"))
      (node (ref "C11") (pin "-") (pinfunction "-_-") (pintype "passive"))
      (node (ref "C12") (pin "2") (pinfunction "2_2") (pintype "passive"))
      (node (ref "C13") (pin "2") (pinfunction "2_2") (pintype "passive"))
      (node (ref "C14") (pin "2") (pinfunction "2_2") (pintype "passive"))
      (node (ref "C15") (pin "2") (pinfunction "2_2") (pintype "passive"))
      (node (ref "C16") (pin "2") (pinfunction "2_2") (pintype "passive"))
      (node (ref "C17") (pin "2") (pinfunction "2_2") (pintype "passive"))
      (node (ref "C18") (pin "2") (pinfunction "2_2") (pintype "passive"))
      (node (ref "C2") (pin "-") (pinfunction "-_-") (pintype "passive"))
      (node (ref "C23") (pin "2") (pinfunction "2_2") (pintype "passive"))
      (node (ref "C27") (pin "2") (pinfunction "2_2") (pintype "passive"))
      (node (ref "C28") (pin "2") (pinfunction "2_2") (pintype "passive"))
      (node (ref "C29") (pin "2") (pinfunction "2_2") (pintype "passive"))
      (node (ref "C3") (pin "-") (pinfunction "-_-") (pintype "passive"))
      (node (ref "C30") (pin "2") (pinfunction "2_2") (pintype "passive"))
      (node (ref "C31") (pin "2") (pinfunction "2_2") (pintype "passive"))
      (node (ref "C32") (pin "2") (pinfunction "2_2") (pintype "passive"))
      (node (ref "C33") (pin "2") (pinfunction "2_2") (pintype "passive"))
      (node (ref "C34") (pin "2") (pinfunction "2_2") (pintype "passive"))
      (node (ref "C35") (pin "2") (pinfunction "2_2") (pintype "passive"))
      (node (ref "C36") (pin "2") (pinfunction "2_2") (pintype "passive"))
      (node (ref "C37") (pin "2") (pinfunction "2_2") (pintype "passive"))
      (node (ref "C38") (pin "2") (pinfunction "2_2") (pintype "passive"))
      (node (ref "C39") (pin "2") (pinfunction "2_2") (pintype "passive"))
      (node (ref "C4") (pin "2") (pinfunction "2_2") (pintype "passive"))
      (node (ref "C40") (pin "2") (pinfunction "2_2") (pintype "passive"))
      (node (ref "C41") (pin "2") (pinfunction "2_2") (pintype "passive"))
      (node (ref "C42") (pin "2") (pinfunction "2_2") (pintype "passive"))
      (node (ref "C43") (pin "2") (pinfunction "2_2") (pintype "passive"))
      (node (ref "C44") (pin "2") (pinfunction "2_2") (pintype "passive"))
      (node (ref "C45") (pin "2") (pinfunction "2_2") (pintype "passive"))
      (node (ref "C46") (pin "2") (pinfunction "2_2") (pintype "passive"))
      (node (ref "C47") (pin "2") (pinfunction "2_2") (pintype "passive"))
      (node (ref "C48") (pin "2") (pinfunction "2_2") (pintype "passive"))
      (node (ref "C49") (pin "2") (pinfunction "2_2") (pintype "passive"))
      (node (ref "C5") (pin "2") (pinfunction "2_2") (pintype "passive"))
      (node (ref "C50") (pin "2") (pinfunction "2_2") (pintype "passive"))
      (node (ref "C51") (pin "2") (pinfunction "2_2") (pintype "passive"))
      (node (ref "C52") (pin "2") (pinfunction "2_2") (pintype "passive"))
      (node (ref "C53") (pin "2") (pinfunction "2_2") (pintype "passive"))
      (node (ref "C54") (pin "2") (pinfunction "2_2") (pintype "passive"))
      (node (ref "C55") (pin "2") (pinfunction "2_2") (pintype "passive"))
      (node (ref "C56") (pin "2") (pinfunction "2_2") (pintype "passive"))
      (node (ref "C57") (pin "2") (pinfunction "2_2") (pintype "passive"))
      (node (ref "C58") (pin "2") (pinfunction "2_2") (pintype "passive"))
      (node (ref "C6") (pin "2") (pinfunction "2_2") (pintype "passive"))
      (node (ref "C7") (pin "2") (pinfunction "2_2") (pintype "passive"))
      (node (ref "C8") (pin "2") (pinfunction "2_2") (pintype "passive"))
      (node (ref "C9") (pin "2") (pinfunction "2_2") (pintype "passive"))
      (node (ref "H1") (pin "B3,0") (pinfunction "MOUNT_B3,0") (pintype "passive"))
      (node (ref "H2") (pin "B3,0") (pinfunction "MOUNT_B3,0") (pintype "passive"))
      (node (ref "H3") (pin "B3,0") (pinfunction "MOUNT_B3,0") (pintype "passive"))
      (node (ref "H4") (pin "B3,0") (pinfunction "MOUNT_B3,0") (pintype "passive"))
      (node (ref "IC2") (pin "1") (pinfunction "DCD_1") (pintype "input"))
      (node (ref "IC2") (pin "2") (pinfunction "RI_2") (pintype "input"))
      (node (ref "IC2") (pin "27") (pinfunction "DSR_27") (pintype "input"))
      (node (ref "IC2") (pin "3") (pinfunction "GND_3") (pintype "power_in"))
      (node (ref "IC2") (pin "EXP") (pinfunction "GND_EXP") (pintype "power_in"))
      (node (ref "IC2") (pin "M") (pinfunction "GND_M") (pintype "power_in"))
      (node (ref "J1") (pin "1") (pinfunction "1_1") (pintype "passive"))
      (node (ref "J1") (pin "2") (pinfunction "2_2") (pintype "passive"))
      (node (ref "JOYPAD1") (pin "3") (pinfunction "3_3") (pintype "passive"))
      (node (ref "JOYPAD1") (pin "S1") (pinfunction "SHIELD_S1") (pintype "bidirectional"))
      (node (ref "JOYPAD1") (pin "S2") (pinfunction "SHIELD_S2") (pintype "bidirectional"))
      (node (ref "JOYPAD1") (pin "S3") (pinfunction "SHIELD_S3") (pintype "bidirectional"))
      (node (ref "JOYPAD2") (pin "3") (pinfunction "3_3") (pintype "passive"))
      (node (ref "JOYPAD2") (pin "S1") (pinfunction "SHIELD_S1") (pintype "bidirectional"))
      (node (ref "JOYPAD2") (pin "S2") (pinfunction "SHIELD_S2") (pintype "bidirectional"))
      (node (ref "JOYPAD2") (pin "S3") (pinfunction "SHIELD_S3") (pintype "bidirectional"))
      (node (ref "JTAG") (pin "10") (pinfunction "10_10") (pintype "passive"))
      (node (ref "JTAG") (pin "2") (pinfunction "2_2") (pintype "passive"))
      (node (ref "MIC_OUT") (pin "SLEEVE") (pinfunction "SLEEVE_SLEEVE") (pintype "passive"))
      (node (ref "POWER") (pin "C") (pinfunction "C_C") (pintype "passive"))
      (node (ref "PS2") (pin "3") (pinfunction "3_3") (pintype "passive"))
      (node (ref "PS2") (pin "S1") (pinfunction "SHIELD_S1") (pintype "bidirectional"))
      (node (ref "PS2") (pin "S2") (pinfunction "SHIELD_S2") (pintype "bidirectional"))
      (node (ref "PS2") (pin "S3") (pinfunction "SHIELD_S3") (pintype "bidirectional"))
      (node (ref "R14") (pin "1") (pinfunction "1_1") (pintype "passive"))
      (node (ref "R15") (pin "1") (pinfunction "1_1") (pintype "passive"))
      (node (ref "R17") (pin "1") (pinfunction "1_1") (pintype "passive"))
      (node (ref "R28") (pin "1") (pinfunction "1_1") (pintype "passive"))
      (node (ref "R31") (pin "2") (pinfunction "2_2") (pintype "passive"))
      (node (ref "R41") (pin "1") (pinfunction "1_1") (pintype "passive"))
      (node (ref "R43") (pin "1") (pinfunction "1_1") (pintype "passive"))
      (node (ref "R5") (pin "1") (pinfunction "1_1") (pintype "passive"))
      (node (ref "R8") (pin "1") (pinfunction "1_1") (pintype "passive"))
      (node (ref "S1") (pin "3") (pinfunction "3_3") (pintype "bidirectional"))
      (node (ref "S1") (pin "4") (pinfunction "4_4") (pintype "bidirectional"))
      (node (ref "SERIAL") (pin "5") (pinfunction "5_5") (pintype "passive"))
      (node (ref "SERIAL") (pin "G1") (pinfunction "SHIELD_G1") (pintype "bidirectional"))
      (node (ref "SERIAL") (pin "G2") (pinfunction "SHIELD_G2") (pintype "bidirectional"))
      (node (ref "TAPE_IN") (pin "SLEEVE") (pinfunction "SLEEVE_SLEEVE") (pintype "passive"))
      (node (ref "TAPE_OUT") (pin "SLEEVE") (pinfunction "SLEEVE_SLEEVE") (pintype "passive"))
      (node (ref "U$1") (pin "3") (pinfunction "GND_3") (pintype "power_in"))
      (node (ref "U$12") (pin "2") (pinfunction "GND_2") (pintype "bidirectional"))
      (node (ref "U$13") (pin "2") (pinfunction "E_2") (pintype "passive"))
      (node (ref "U$14") (pin "2") (pinfunction "E_2") (pintype "passive"))
      (node (ref "U$15") (pin "2") (pinfunction "E_2") (pintype "passive"))
      (node (ref "U$16") (pin "4") (pinfunction "VSS_4") (pintype "bidirectional"))
      (node (ref "U$17") (pin "1") (pinfunction "NC_1") (pintype "bidirectional"))
      (node (ref "U$17") (pin "2") (pinfunction "A1_2") (pintype "bidirectional"))
      (node (ref "U$17") (pin "4") (pinfunction "VSS_4") (pintype "bidirectional"))
      (node (ref "U$17") (pin "7") (pinfunction "WP_7") (pintype "bidirectional"))
      (node (ref "U$18") (pin "2") (pinfunction "E_2") (pintype "passive"))
      (node (ref "U$19") (pin "2") (pinfunction "E_2") (pintype "passive"))
      (node (ref "U$2") (pin "23") (pinfunction "VSS1_23") (pintype "bidirectional"))
      (node (ref "U$2") (pin "3") (pinfunction "VSSQ0_3") (pintype "bidirectional"))
      (node (ref "U$2") (pin "38") (pinfunction "VSSQ3_38") (pintype "bidirectional"))
      (node (ref "U$2") (pin "42") (pinfunction "VSSQ2_42") (pintype "bidirectional"))
      (node (ref "U$2") (pin "44") (pinfunction "VSS0_44") (pintype "bidirectional"))
      (node (ref "U$2") (pin "7") (pinfunction "VSSQ1_7") (pintype "bidirectional"))
      (node (ref "U$20") (pin "2") (pinfunction "E_2") (pintype "passive"))
      (node (ref "U$21") (pin "2") (pinfunction "E_2") (pintype "passive"))
      (node (ref "U$3") (pin "A") (pinfunction "A_A") (pintype "passive"))
      (node (ref "U$4") (pin "15") (pinfunction "GND_15") (pintype "bidirectional"))
      (node (ref "U$5") (pin "1") (pinfunction "ADJ_1") (pintype "bidirectional"))
      (node (ref "U$6") (pin "P$1") (pinfunction "-_P$1") (pintype "passive"))
      (node (ref "U$7") (pin "1") (pinfunction "ADJ_1") (pintype "bidirectional"))
      (node (ref "U$8") (pin "1") (pinfunction "ADJ_1") (pintype "bidirectional"))
      (node (ref "U$9") (pin "1") (pinfunction "ADJ_1") (pintype "bidirectional"))
      (node (ref "U1") (pin "108") (pinfunction "GNDA2_108") (pintype "power_in"))
      (node (ref "U1") (pin "118") (pinfunction "GND_118") (pintype "power_in"))
      (node (ref "U1") (pin "123") (pinfunction "GND_123") (pintype "power_in"))
      (node (ref "U1") (pin "131") (pinfunction "GND_131") (pintype "power_in"))
      (node (ref "U1") (pin "140") (pinfunction "GND_140") (pintype "power_in"))
      (node (ref "U1") (pin "145") (pinfunction "EXP_145") (pintype "power_in"))
      (node (ref "U1") (pin "19") (pinfunction "GND_19") (pintype "power_in"))
      (node (ref "U1") (pin "22") (pinfunction "GND_22") (pintype "power_in"))
      (node (ref "U1") (pin "24") (pinfunction "CLK2_24") (pintype "bidirectional"))
      (node (ref "U1") (pin "27") (pinfunction "GND_27") (pintype "power_in"))
      (node (ref "U1") (pin "36") (pinfunction "GNDA1_36") (pintype "power_in"))
      (node (ref "U1") (pin "4") (pinfunction "GND_4") (pintype "power_in"))
      (node (ref "U1") (pin "41") (pinfunction "GND_41") (pintype "power_in"))
      (node (ref "U1") (pin "48") (pinfunction "GND_48") (pintype "power_in"))
      (node (ref "U1") (pin "57") (pinfunction "GND_57") (pintype "power_in"))
      (node (ref "U1") (pin "63") (pinfunction "GND_63") (pintype "power_in"))
      (node (ref "U1") (pin "79") (pinfunction "GND_79") (pintype "power_in"))
      (node (ref "U1") (pin "82") (pinfunction "GND_82") (pintype "power_in"))
      (node (ref "U1") (pin "88") (pinfunction "CLK7_88") (pintype "bidirectional"))
      (node (ref "U1") (pin "89") (pinfunction "CLK6_89") (pintype "bidirectional"))
      (node (ref "U1") (pin "90") (pinfunction "CLK5_90") (pintype "bidirectional"))
      (node (ref "U1") (pin "91") (pinfunction "CLK4_91") (pintype "bidirectional"))
      (node (ref "U1") (pin "94") (pinfunction "MSEL0_94") (pintype "bidirectional"))
      (node (ref "U1") (pin "95") (pinfunction "GND_95") (pintype "power_in"))
      (node (ref "U1") (pin "97") (pinfunction "MSEL2_97") (pintype "bidirectional"))
      (node (ref "VGA") (pin "10") (pinfunction "10_10") (pintype "passive"))
      (node (ref "VGA") (pin "5") (pinfunction "5_5") (pintype "passive"))
      (node (ref "VGA") (pin "6") (pinfunction "6_6") (pintype "passive"))
      (node (ref "VGA") (pin "7") (pinfunction "7_7") (pintype "passive"))
      (node (ref "VGA") (pin "8") (pinfunction "8_8") (pintype "passive"))
      (node (ref "VGA") (pin "S1") (pinfunction "SHIELD_S1") (pintype "bidirectional"))
      (node (ref "VGA") (pin "S2") (pinfunction "SHIELD_S2") (pintype "bidirectional"))
      (node (ref "X1") (pin "4") (pinfunction "4_4") (pintype "passive"))
      (node (ref "X1") (pin "S1") (pinfunction "S1_S1") (pintype "passive"))
      (node (ref "X1") (pin "S2") (pinfunction "S2_S2") (pintype "passive"))
    )
    (net (code "48") (name "/HSYNC") (class "Default")
      (node (ref "R18") (pin "2") (pinfunction "2_2") (pintype "passive"))
      (node (ref "U1") (pin "84") (pinfunction "IO_84") (pintype "bidirectional"))
    )
    (net (code "49") (name "/I2C_SCL") (class "Default")
      (node (ref "U$17") (pin "6") (pinfunction "SCL_6") (pintype "bidirectional"))
      (node (ref "U1") (pin "143") (pinfunction "IO_143") (pintype "bidirectional"))
    )
    (net (code "50") (name "/I2C_SDA") (class "Default")
      (node (ref "U$17") (pin "5") (pinfunction "SDA_5") (pintype "bidirectional"))
      (node (ref "U1") (pin "144") (pinfunction "IO_144") (pintype "bidirectional"))
    )
    (net (code "51") (name "/JP1_CLK") (class "Default")
      (node (ref "JOYPAD1") (pin "5") (pinfunction "5_5") (pintype "passive"))
      (node (ref "R35") (pin "2") (pinfunction "2_2") (pintype "passive"))
      (node (ref "U$18") (pin "3") (pinfunction "C_3") (pintype "passive"))
    )
    (net (code "52") (name "/JP1_CLK_Q") (class "Default")
      (node (ref "R39") (pin "1") (pinfunction "1_1") (pintype "passive"))
      (node (ref "U1") (pin "77") (pinfunction "IO_77") (pintype "bidirectional"))
    )
    (net (code "53") (name "/JP1_DATA") (class "Default")
      (node (ref "JOYPAD1") (pin "1") (pinfunction "1_1") (pintype "passive"))
      (node (ref "R40") (pin "2") (pinfunction "2_2") (pintype "passive"))
    )
    (net (code "54") (name "/JP1_DATA_D") (class "Default")
      (node (ref "R40") (pin "1") (pinfunction "1_1") (pintype "passive"))
      (node (ref "R41") (pin "2") (pinfunction "2_2") (pintype "passive"))
      (node (ref "U1") (pin "75") (pinfunction "IO_75") (pintype "bidirectional"))
    )
    (net (code "55") (name "/JP1_LATCH") (class "Default")
      (node (ref "JOYPAD1") (pin "6") (pinfunction "6_6") (pintype "passive"))
      (node (ref "R34") (pin "2") (pinfunction "2_2") (pintype "passive"))
      (node (ref "U$19") (pin "3") (pinfunction "C_3") (pintype "passive"))
    )
    (net (code "56") (name "/JP1_LATCH_Q") (class "Default")
      (node (ref "R38") (pin "1") (pinfunction "1_1") (pintype "passive"))
      (node (ref "U1") (pin "76") (pinfunction "IO_76") (pintype "bidirectional"))
    )
    (net (code "57") (name "/JP2_CLK") (class "Default")
      (node (ref "JOYPAD2") (pin "5") (pinfunction "5_5") (pintype "passive"))
      (node (ref "R33") (pin "2") (pinfunction "2_2") (pintype "passive"))
      (node (ref "U$20") (pin "3") (pinfunction "C_3") (pintype "passive"))
    )
    (net (code "58") (name "/JP2_CLK_Q") (class "Default")
      (node (ref "R37") (pin "1") (pinfunction "1_1") (pintype "passive"))
      (node (ref "U1") (pin "83") (pinfunction "IO_83") (pintype "bidirectional"))
    )
    (net (code "59") (name "/JP2_DATA") (class "Default")
      (node (ref "JOYPAD2") (pin "1") (pinfunction "1_1") (pintype "passive"))
      (node (ref "R42") (pin "2") (pinfunction "2_2") (pintype "passive"))
    )
    (net (code "60") (name "/JP2_DATA_D") (class "Default")
      (node (ref "R42") (pin "1") (pinfunction "1_1") (pintype "passive"))
      (node (ref "R43") (pin "2") (pinfunction "2_2") (pintype "passive"))
      (node (ref "U1") (pin "74") (pinfunction "IO_74") (pintype "bidirectional"))
    )
    (net (code "61") (name "/JP2_LATCH") (class "Default")
      (node (ref "JOYPAD2") (pin "6") (pinfunction "6_6") (pintype "passive"))
      (node (ref "R32") (pin "2") (pinfunction "2_2") (pintype "passive"))
      (node (ref "U$21") (pin "3") (pinfunction "C_3") (pintype "passive"))
    )
    (net (code "62") (name "/JP2_LATCH_Q") (class "Default")
      (node (ref "R36") (pin "1") (pinfunction "1_1") (pintype "passive"))
      (node (ref "U1") (pin "80") (pinfunction "IO_80") (pintype "bidirectional"))
    )
    (net (code "63") (name "/LED_0") (class "Default")
      (node (ref "LED_0") (pin "C") (pinfunction "C_C") (pintype "passive"))
      (node (ref "U1") (pin "110") (pinfunction "IO_110") (pintype "bidirectional"))
    )
    (net (code "64") (name "/LED_1") (class "Default")
      (node (ref "LED_1") (pin "C") (pinfunction "C_C") (pintype "passive"))
      (node (ref "U1") (pin "111") (pinfunction "IO_111") (pintype "bidirectional"))
    )
    (net (code "65") (name "/LED_2") (class "Default")
      (node (ref "LED_2") (pin "C") (pinfunction "C_C") (pintype "passive"))
      (node (ref "U1") (pin "112") (pinfunction "IO_112") (pintype "bidirectional"))
    )
    (net (code "66") (name "/LED_3") (class "Default")
      (node (ref "LED_3") (pin "C") (pinfunction "C_C") (pintype "passive"))
      (node (ref "U1") (pin "113") (pinfunction "IO_113") (pintype "bidirectional"))
    )
    (net (code "67") (name "/PS2_CLK") (class "Default")
      (node (ref "PS2") (pin "5") (pinfunction "5_5") (pintype "passive"))
      (node (ref "R11") (pin "2") (pinfunction "2_2") (pintype "passive"))
      (node (ref "R13") (pin "2") (pinfunction "2_2") (pintype "passive"))
      (node (ref "U$14") (pin "3") (pinfunction "C_3") (pintype "passive"))
    )
    (net (code "68") (name "/PS2_CLK_D") (class "Default")
      (node (ref "R13") (pin "1") (pinfunction "1_1") (pintype "passive"))
      (node (ref "R15") (pin "2") (pinfunction "2_2") (pintype "passive"))
      (node (ref "U1") (pin "120") (pinfunction "IO_120") (pintype "bidirectional"))
    )
    (net (code "69") (name "/PS2_CLK_Q") (class "Default")
      (node (ref "R3") (pin "1") (pinfunction "1_1") (pintype "passive"))
      (node (ref "U1") (pin "124") (pinfunction "IO_124") (pintype "bidirectional"))
    )
    (net (code "70") (name "/PS2_DATA") (class "Default")
      (node (ref "PS2") (pin "1") (pinfunction "1_1") (pintype "passive"))
      (node (ref "R10") (pin "2") (pinfunction "2_2") (pintype "passive"))
      (node (ref "R12") (pin "2") (pinfunction "2_2") (pintype "passive"))
      (node (ref "U$13") (pin "3") (pinfunction "C_3") (pintype "passive"))
    )
    (net (code "71") (name "/PS2_DATA_D") (class "Default")
      (node (ref "R12") (pin "1") (pinfunction "1_1") (pintype "passive"))
      (node (ref "R14") (pin "2") (pinfunction "2_2") (pintype "passive"))
      (node (ref "U1") (pin "119") (pinfunction "IO_119") (pintype "bidirectional"))
    )
    (net (code "72") (name "/PS2_DATA_Q") (class "Default")
      (node (ref "R2") (pin "1") (pinfunction "1_1") (pintype "passive"))
      (node (ref "U1") (pin "121") (pinfunction "IO_121") (pintype "bidirectional"))
    )
    (net (code "73") (name "/R0") (class "Default")
      (node (ref "R24") (pin "1") (pinfunction "1_1") (pintype "passive"))
      (node (ref "U1") (pin "100") (pinfunction "IO_100") (pintype "bidirectional"))
    )
    (net (code "74") (name "/R1") (class "Default")
      (node (ref "R25") (pin "1") (pinfunction "1_1") (pintype "passive"))
      (node (ref "U1") (pin "101") (pinfunction "IO_101") (pintype "bidirectional"))
    )
    (net (code "75") (name "/RESET") (class "Default")
      (node (ref "C57") (pin "1") (pinfunction "1_1") (pintype "passive"))
      (node (ref "R44") (pin "1") (pinfunction "1_1") (pintype "passive"))
      (node (ref "S1") (pin "2") (pinfunction "2_2") (pintype "bidirectional"))
      (node (ref "U1") (pin "25") (pinfunction "CLK3_25") (pintype "bidirectional"))
    )
    (net (code "76") (name "/RTS") (class "Default")
      (node (ref "U$4") (pin "9") (pinfunction "R2_OUT_9") (pintype "bidirectional"))
      (node (ref "U1") (pin "103") (pinfunction "IO_103") (pintype "bidirectional"))
    )
    (net (code "77") (name "/RW") (class "Default")
      (node (ref "U$2") (pin "12") (pinfunction "~{W}_12") (pintype "bidirectional"))
      (node (ref "U1") (pin "65") (pinfunction "IO_65") (pintype "bidirectional"))
    )
    (net (code "78") (name "/RXD") (class "Default")
      (node (ref "U$4") (pin "12") (pinfunction "R1_OUT_12") (pintype "bidirectional"))
      (node (ref "U1") (pin "106") (pinfunction "IO_106") (pintype "bidirectional"))
    )
    (net (code "79") (name "/SDRAM_CLK") (class "Default")
      (node (ref "U$2") (pin "32") (pinfunction "CLK_32") (pintype "bidirectional"))
      (node (ref "U1") (pin "43") (pinfunction "IO_43") (pintype "bidirectional"))
    )
    (net (code "80") (name "/TAPE_IN") (class "Default")
      (node (ref "U$1") (pin "4") (pinfunction "Y_4") (pintype "output"))
      (node (ref "U1") (pin "127") (pinfunction "IO_127") (pintype "bidirectional"))
    )
    (net (code "81") (name "/TAPE_OUT") (class "Default")
      (node (ref "R4") (pin "1") (pinfunction "1_1") (pintype "passive"))
      (node (ref "R9") (pin "1") (pinfunction "1_1") (pintype "passive"))
      (node (ref "U1") (pin "125") (pinfunction "IO_125") (pintype "bidirectional"))
    )
    (net (code "82") (name "/TCK") (class "Default")
      (node (ref "JTAG") (pin "1") (pinfunction "1_1") (pintype "passive"))
      (node (ref "R28") (pin "2") (pinfunction "2_2") (pintype "passive"))
      (node (ref "U1") (pin "16") (pinfunction "TCK_16") (pintype "bidirectional"))
    )
    (net (code "83") (name "/TDI") (class "Default")
      (node (ref "JTAG") (pin "9") (pinfunction "9_9") (pintype "passive"))
      (node (ref "R30") (pin "2") (pinfunction "2_2") (pintype "passive"))
      (node (ref "U1") (pin "15") (pinfunction "TDI_15") (pintype "bidirectional"))
    )
    (net (code "84") (name "/TDO") (class "Default")
      (node (ref "JTAG") (pin "3") (pinfunction "3_3") (pintype "passive"))
      (node (ref "U1") (pin "20") (pinfunction "TDO_20") (pintype "bidirectional"))
    )
    (net (code "85") (name "/TMS") (class "Default")
      (node (ref "JTAG") (pin "5") (pinfunction "5_5") (pintype "passive"))
      (node (ref "R29") (pin "2") (pinfunction "2_2") (pintype "passive"))
      (node (ref "U1") (pin "18") (pinfunction "TMS_18") (pintype "bidirectional"))
    )
    (net (code "86") (name "/TXD") (class "Default")
      (node (ref "U$4") (pin "11") (pinfunction "T1_IN_11") (pintype "bidirectional"))
      (node (ref "U1") (pin "105") (pinfunction "IO_105") (pintype "bidirectional"))
    )
    (net (code "87") (name "/VSYNC") (class "Default")
      (node (ref "R19") (pin "2") (pinfunction "2_2") (pintype "passive"))
      (node (ref "U1") (pin "85") (pinfunction "IO_85") (pintype "bidirectional"))
    )
    (net (code "88") (name "/~{CAS}") (class "Default")
      (node (ref "U$2") (pin "13") (pinfunction "~{CAS}_13") (pintype "bidirectional"))
      (node (ref "U1") (pin "66") (pinfunction "IO_66") (pintype "bidirectional"))
    )
    (net (code "89") (name "/~{CE}") (class "Default")
      (node (ref "AS") (pin "6") (pinfunction "6_6") (pintype "passive"))
      (node (ref "R31") (pin "1") (pinfunction "1_1") (pintype "passive"))
      (node (ref "U1") (pin "21") (pinfunction "NCE_21") (pintype "bidirectional"))
    )
    (net (code "90") (name "/~{CONFIG}") (class "Default")
      (node (ref "AS") (pin "5") (pinfunction "5_5") (pintype "passive"))
      (node (ref "R46") (pin "2") (pinfunction "2_2") (pintype "passive"))
      (node (ref "U1") (pin "14") (pinfunction "NCONFIG_14") (pintype "bidirectional"))
    )
    (net (code "91") (name "/~{CSO}") (class "Default")
      (node (ref "AS") (pin "8") (pinfunction "8_8") (pintype "passive"))
      (node (ref "U$16") (pin "1") (pinfunction "~{CS}_1") (pintype "bidirectional"))
      (node (ref "U1") (pin "8") (pinfunction "IO_8") (pintype "bidirectional"))
    )
    (net (code "92") (name "/~{CS}") (class "Default")
      (node (ref "U$2") (pin "15") (pinfunction "~{CS}_15") (pintype "bidirectional"))
      (node (ref "U1") (pin "68") (pinfunction "IO_68") (pintype "bidirectional"))
    )
    (net (code "93") (name "/~{RAS}") (class "Default")
      (node (ref "U$2") (pin "14") (pinfunction "~{RAS}_14") (pintype "bidirectional"))
      (node (ref "U1") (pin "67") (pinfunction "IO_67") (pintype "bidirectional"))
    )
    (net (code "94") (name "Net-(AUDIO_OUT-PadRING)") (class "Default")
      (node (ref "AUDIO_OUT") (pin "RING") (pinfunction "RING_RING") (pintype "passive"))
      (node (ref "AUDIO_OUT") (pin "TIP") (pinfunction "TIP_TIP") (pintype "passive"))
      (node (ref "C21") (pin "1") (pinfunction "1_1") (pintype "passive"))
      (node (ref "R5") (pin "2") (pinfunction "2_2") (pintype "passive"))
    )
    (net (code "95") (name "Net-(C19-Pad2)") (class "Default")
      (node (ref "C19") (pin "2") (pinfunction "2_2") (pintype "passive"))
      (node (ref "R16") (pin "2") (pinfunction "2_2") (pintype "passive"))
    )
    (net (code "96") (name "Net-(C20-Pad1)") (class "Default")
      (node (ref "C20") (pin "1") (pinfunction "1_1") (pintype "passive"))
      (node (ref "TAPE_OUT") (pin "RING") (pinfunction "RING_RING") (pintype "passive"))
      (node (ref "TAPE_OUT") (pin "TIP") (pinfunction "TIP_TIP") (pintype "passive"))
    )
    (net (code "97") (name "Net-(C21-Pad2)") (class "Default")
      (node (ref "C21") (pin "2") (pinfunction "2_2") (pintype "passive"))
      (node (ref "R6") (pin "2") (pinfunction "2_2") (pintype "passive"))
    )
    (net (code "98") (name "Net-(C22-Pad1)") (class "Default")
      (node (ref "C22") (pin "1") (pinfunction "1_1") (pintype "passive"))
      (node (ref "MIC_OUT") (pin "TIP") (pinfunction "TIP_TIP") (pintype "passive"))
      (node (ref "R8") (pin "2") (pinfunction "2_2") (pintype "passive"))
    )
    (net (code "99") (name "Net-(C22-Pad2)") (class "Default")
      (node (ref "C22") (pin "2") (pinfunction "2_2") (pintype "passive"))
      (node (ref "R9") (pin "2") (pinfunction "2_2") (pintype "passive"))
    )
    (net (code "100") (name "Net-(D1-PadA)") (class "Default")
      (node (ref "D1") (pin "A") (pinfunction "A_A") (pintype "passive"))
      (node (ref "J1") (pin "3") (pinfunction "3_3") (pintype "passive"))
    )
    (net (code "101") (name "Net-(IC2-D+)") (class "Default")
      (node (ref "IC2") (pin "4") (pinfunction "D+_4") (pintype "bidirectional"))
      (node (ref "X1") (pin "3") (pinfunction "3_3") (pintype "passive"))
    )
    (net (code "102") (name "Net-(IC2-D-)") (class "Default")
      (node (ref "IC2") (pin "5") (pinfunction "D-_5") (pintype "bidirectional"))
      (node (ref "X1") (pin "2") (pinfunction "2_2") (pintype "passive"))
    )
    (net (code "103") (name "Net-(IC2-REGIN)") (class "Default")
      (node (ref "C13") (pin "1") (pinfunction "1_1") (pintype "passive"))
      (node (ref "D2") (pin "A") (pinfunction "A_A") (pintype "passive"))
      (node (ref "IC2") (pin "7") (pinfunction "REGIN_7") (pintype "passive"))
      (node (ref "IC2") (pin "8") (pinfunction "VBUS_8") (pintype "input"))
      (node (ref "X1") (pin "1") (pinfunction "1_1") (pintype "passive"))
    )
    (net (code "104") (name "Net-(IC2-VDD)") (class "Default")
      (node (ref "C12") (pin "1") (pinfunction "1_1") (pintype "passive"))
      (node (ref "C14") (pin "1") (pinfunction "1_1") (pintype "passive"))
      (node (ref "IC2") (pin "6") (pinfunction "VDD_6") (pintype "power_in"))
      (node (ref "R1") (pin "1") (pinfunction "1_1") (pintype "passive"))
    )
    (net (code "105") (name "Net-(IC2-~{RST})") (class "Default")
      (node (ref "IC2") (pin "9") (pinfunction "~{RST}_9") (pintype "bidirectional"))
      (node (ref "R1") (pin "2") (pinfunction "2_2") (pintype "passive"))
    )
    (net (code "106") (name "Net-(LED_0-PadA)") (class "Default")
      (node (ref "LED_0") (pin "A") (pinfunction "A_A") (pintype "passive"))
      (node (ref "R55") (pin "2") (pinfunction "2_2") (pintype "passive"))
    )
    (net (code "107") (name "Net-(LED_1-PadA)") (class "Default")
      (node (ref "LED_1") (pin "A") (pinfunction "A_A") (pintype "passive"))
      (node (ref "R54") (pin "2") (pinfunction "2_2") (pintype "passive"))
    )
    (net (code "108") (name "Net-(LED_2-PadA)") (class "Default")
      (node (ref "LED_2") (pin "A") (pinfunction "A_A") (pintype "passive"))
      (node (ref "R53") (pin "2") (pinfunction "2_2") (pintype "passive"))
    )
    (net (code "109") (name "Net-(LED_3-PadA)") (class "Default")
      (node (ref "LED_3") (pin "A") (pinfunction "A_A") (pintype "passive"))
      (node (ref "R52") (pin "2") (pinfunction "2_2") (pintype "passive"))
    )
    (net (code "110") (name "Net-(POWER-PadA)") (class "Default")
      (node (ref "POWER") (pin "A") (pinfunction "A_A") (pintype "passive"))
      (node (ref "R56") (pin "2") (pinfunction "2_2") (pintype "passive"))
    )
    (net (code "111") (name "Net-(R18-Pad1)") (class "Default")
      (node (ref "R18") (pin "1") (pinfunction "1_1") (pintype "passive"))
      (node (ref "VGA") (pin "13") (pinfunction "13_13") (pintype "passive"))
    )
    (net (code "112") (name "Net-(R19-Pad1)") (class "Default")
      (node (ref "R19") (pin "1") (pinfunction "1_1") (pintype "passive"))
      (node (ref "VGA") (pin "14") (pinfunction "14_14") (pintype "passive"))
    )
    (net (code "113") (name "Net-(R20-Pad2)") (class "Default")
      (node (ref "R20") (pin "2") (pinfunction "2_2") (pintype "passive"))
      (node (ref "R21") (pin "2") (pinfunction "2_2") (pintype "passive"))
      (node (ref "VGA") (pin "2") (pinfunction "2_2") (pintype "passive"))
    )
    (net (code "114") (name "Net-(R22-Pad2)") (class "Default")
      (node (ref "R22") (pin "2") (pinfunction "2_2") (pintype "passive"))
      (node (ref "R23") (pin "2") (pinfunction "2_2") (pintype "passive"))
      (node (ref "VGA") (pin "3") (pinfunction "3_3") (pintype "passive"))
    )
    (net (code "115") (name "Net-(R24-Pad2)") (class "Default")
      (node (ref "R24") (pin "2") (pinfunction "2_2") (pintype "passive"))
      (node (ref "R25") (pin "2") (pinfunction "2_2") (pintype "passive"))
      (node (ref "VGA") (pin "1") (pinfunction "1_1") (pintype "passive"))
    )
    (net (code "116") (name "Net-(U$1-A)") (class "Default")
      (node (ref "C19") (pin "1") (pinfunction "1_1") (pintype "passive"))
      (node (ref "U$1") (pin "2") (pinfunction "A_2") (pintype "input"))
      (node (ref "U$3") (pin "C") (pinfunction "C_C") (pintype "passive"))
    )
    (net (code "117") (name "Net-(U$4-C1+)") (class "Default")
      (node (ref "C25") (pin "1") (pinfunction "1_1") (pintype "passive"))
      (node (ref "U$4") (pin "1") (pinfunction "C1+_1") (pintype "bidirectional"))
    )
    (net (code "118") (name "Net-(U$4-C1-)") (class "Default")
      (node (ref "C25") (pin "2") (pinfunction "2_2") (pintype "passive"))
      (node (ref "U$4") (pin "3") (pinfunction "C1-_3") (pintype "bidirectional"))
    )
    (net (code "119") (name "Net-(U$4-C2+)") (class "Default")
      (node (ref "C26") (pin "1") (pinfunction "1_1") (pintype "passive"))
      (node (ref "U$4") (pin "4") (pinfunction "C2+_4") (pintype "bidirectional"))
    )
    (net (code "120") (name "Net-(U$4-C2-)") (class "Default")
      (node (ref "C26") (pin "2") (pinfunction "2_2") (pintype "passive"))
      (node (ref "U$4") (pin "5") (pinfunction "C2-_5") (pintype "bidirectional"))
    )
    (net (code "121") (name "Net-(U$4-R1_IN)") (class "Default")
      (node (ref "SERIAL") (pin "3") (pinfunction "3_3") (pintype "passive"))
      (node (ref "U$4") (pin "13") (pinfunction "R1_IN_13") (pintype "bidirectional"))
    )
    (net (code "122") (name "Net-(U$4-R2_IN)") (class "Default")
      (node (ref "SERIAL") (pin "8") (pinfunction "8_8") (pintype "passive"))
      (node (ref "U$4") (pin "8") (pinfunction "R2_IN_8") (pintype "bidirectional"))
    )
    (net (code "123") (name "Net-(U$4-T1_OUT)") (class "Default")
      (node (ref "SERIAL") (pin "2") (pinfunction "2_2") (pintype "passive"))
      (node (ref "U$4") (pin "14") (pinfunction "T1_OUT_14") (pintype "bidirectional"))
    )
    (net (code "124") (name "Net-(U$4-T2_OUT)") (class "Default")
      (node (ref "SERIAL") (pin "7") (pinfunction "7_7") (pintype "passive"))
      (node (ref "U$4") (pin "7") (pinfunction "T2_OUT_7") (pintype "bidirectional"))
    )
    (net (code "125") (name "Net-(U$4-V+)") (class "Default")
      (node (ref "C24") (pin "2") (pinfunction "2_2") (pintype "passive"))
      (node (ref "U$4") (pin "2") (pinfunction "V+_2") (pintype "bidirectional"))
    )
    (net (code "126") (name "Net-(U$4-V-)") (class "Default")
      (node (ref "C23") (pin "1") (pinfunction "1_1") (pintype "passive"))
      (node (ref "U$4") (pin "6") (pinfunction "V-_6") (pintype "bidirectional"))
    )
    (net (code "127") (name "Net-(U$5-IN)") (class "Default")
      (node (ref "C4") (pin "1") (pinfunction "1_1") (pintype "passive"))
      (node (ref "D1") (pin "C") (pinfunction "C_C") (pintype "passive"))
      (node (ref "U$5") (pin "3") (pinfunction "IN_3") (pintype "bidirectional"))
      (node (ref "U$6") (pin "P$2") (pinfunction "+_P$2") (pintype "passive"))
    )
    (net (code "128") (name "Net-(U$12-OUT)") (class "Default")
      (node (ref "R27") (pin "1") (pinfunction "1_1") (pintype "passive"))
      (node (ref "U$12") (pin "3") (pinfunction "OUT_3") (pintype "bidirectional"))
    )
    (net (code "129") (name "Net-(U$13-B)") (class "Default")
      (node (ref "R2") (pin "2") (pinfunction "2_2") (pintype "passive"))
      (node (ref "U$13") (pin "1") (pinfunction "B_1") (pintype "passive"))
    )
    (net (code "130") (name "Net-(U$14-B)") (class "Default")
      (node (ref "R3") (pin "2") (pinfunction "2_2") (pintype "passive"))
      (node (ref "U$14") (pin "1") (pinfunction "B_1") (pintype "passive"))
    )
    (net (code "131") (name "Net-(U$15-B)") (class "Default")
      (node (ref "R4") (pin "2") (pinfunction "2_2") (pintype "passive"))
      (node (ref "U$15") (pin "1") (pinfunction "B_1") (pintype "passive"))
    )
    (net (code "132") (name "Net-(U$15-C)") (class "Default")
      (node (ref "C20") (pin "2") (pinfunction "2_2") (pintype "passive"))
      (node (ref "R7") (pin "2") (pinfunction "2_2") (pintype "passive"))
      (node (ref "U$15") (pin "3") (pinfunction "C_3") (pintype "passive"))
    )
    (net (code "133") (name "Net-(U$16-SO)") (class "Default")
      (node (ref "R26") (pin "2") (pinfunction "2_2") (pintype "passive"))
      (node (ref "U$16") (pin "2") (pinfunction "SO_2") (pintype "bidirectional"))
    )
    (net (code "134") (name "Net-(U$18-B)") (class "Default")
      (node (ref "R39") (pin "2") (pinfunction "2_2") (pintype "passive"))
      (node (ref "U$18") (pin "1") (pinfunction "B_1") (pintype "passive"))
    )
    (net (code "135") (name "Net-(U$19-B)") (class "Default")
      (node (ref "R38") (pin "2") (pinfunction "2_2") (pintype "passive"))
      (node (ref "U$19") (pin "1") (pinfunction "B_1") (pintype "passive"))
    )
    (net (code "136") (name "Net-(U$20-B)") (class "Default")
      (node (ref "R37") (pin "2") (pinfunction "2_2") (pintype "passive"))
      (node (ref "U$20") (pin "1") (pinfunction "B_1") (pintype "passive"))
    )
    (net (code "137") (name "Net-(U$21-B)") (class "Default")
      (node (ref "R36") (pin "2") (pinfunction "2_2") (pintype "passive"))
      (node (ref "U$21") (pin "1") (pinfunction "B_1") (pintype "passive"))
    )
    (net (code "138") (name "Net-(U1-NSTATUS)") (class "Default")
      (node (ref "R45") (pin "2") (pinfunction "2_2") (pintype "passive"))
      (node (ref "U1") (pin "9") (pinfunction "NSTATUS_9") (pintype "bidirectional"))
    )
    (net (code "139") (name "Net-(U1-VCCD_PLL1)") (class "Default")
      (node (ref "C17") (pin "1") (pinfunction "1_1") (pintype "passive"))
      (node (ref "U$10") (pin "1") (pinfunction "1_1") (pintype "passive"))
      (node (ref "U1") (pin "37") (pinfunction "VCCD_PLL1_37") (pintype "power_in"))
    )
    (net (code "140") (name "Net-(U1-VCCD_PLL2)") (class "Default")
      (node (ref "C18") (pin "1") (pinfunction "1_1") (pintype "passive"))
      (node (ref "U$11") (pin "1") (pinfunction "1_1") (pintype "passive"))
      (node (ref "U1") (pin "109") (pinfunction "VCCD_PLL2_109") (pintype "power_in"))
    )
    (net (code "141") (name "unconnected-(AUDIO_OUT-PadRING_SWITCH)") (class "Default")
      (node (ref "AUDIO_OUT") (pin "RING_SWITCH") (pinfunction "RING_SWITCH_RING_SWITCH") (pintype "passive"))
    )
    (net (code "142") (name "unconnected-(AUDIO_OUT-PadTIP_SWITCH)") (class "Default")
      (node (ref "AUDIO_OUT") (pin "TIP_SWITCH") (pinfunction "TIP_SWITCH_TIP_SWITCH") (pintype "passive"))
    )
    (net (code "143") (name "unconnected-(BUTTON_0-Pad1)") (class "Default")
      (node (ref "BUTTON_0") (pin "1") (pinfunction "1_1") (pintype "bidirectional"))
    )
    (net (code "144") (name "unconnected-(BUTTON_0-Pad4)") (class "Default")
      (node (ref "BUTTON_0") (pin "4") (pinfunction "4_4") (pintype "bidirectional"))
    )
    (net (code "145") (name "unconnected-(BUTTON_1-Pad1)") (class "Default")
      (node (ref "BUTTON_1") (pin "1") (pinfunction "1_1") (pintype "bidirectional"))
    )
    (net (code "146") (name "unconnected-(BUTTON_1-Pad4)") (class "Default")
      (node (ref "BUTTON_1") (pin "4") (pinfunction "4_4") (pintype "bidirectional"))
    )
    (net (code "147") (name "unconnected-(BUTTON_2-Pad1)") (class "Default")
      (node (ref "BUTTON_2") (pin "1") (pinfunction "1_1") (pintype "bidirectional"))
    )
    (net (code "148") (name "unconnected-(BUTTON_2-Pad4)") (class "Default")
      (node (ref "BUTTON_2") (pin "4") (pinfunction "4_4") (pintype "bidirectional"))
    )
    (net (code "149") (name "unconnected-(BUTTON_3-Pad1)") (class "Default")
      (node (ref "BUTTON_3") (pin "1") (pinfunction "1_1") (pintype "bidirectional"))
    )
    (net (code "150") (name "unconnected-(BUTTON_3-Pad4)") (class "Default")
      (node (ref "BUTTON_3") (pin "4") (pinfunction "4_4") (pintype "bidirectional"))
    )
    (net (code "151") (name "unconnected-(IC2-DTR-Pad28)") (class "Default")
      (node (ref "IC2") (pin "28") (pinfunction "DTR_28") (pintype "output"))
    )
    (net (code "152") (name "unconnected-(IC2-SUSPEND-Pad12)") (class "Default")
      (node (ref "IC2") (pin "12") (pinfunction "SUSPEND_12") (pintype "output"))
    )
    (net (code "153") (name "unconnected-(IC2-~{SUSPEND}-Pad11)") (class "Default")
      (node (ref "IC2") (pin "11") (pinfunction "~{SUSPEND}_11") (pintype "output"))
    )
    (net (code "154") (name "unconnected-(JOYPAD1-Pad2)") (class "Default")
      (node (ref "JOYPAD1") (pin "2") (pinfunction "2_2") (pintype "passive"))
    )
    (net (code "155") (name "unconnected-(JOYPAD2-Pad2)") (class "Default")
      (node (ref "JOYPAD2") (pin "2") (pinfunction "2_2") (pintype "passive"))
    )
    (net (code "156") (name "unconnected-(JTAG-Pad6)") (class "Default")
      (node (ref "JTAG") (pin "6") (pinfunction "6_6") (pintype "passive"))
    )
    (net (code "157") (name "unconnected-(JTAG-Pad7)") (class "Default")
      (node (ref "JTAG") (pin "7") (pinfunction "7_7") (pintype "passive"))
    )
    (net (code "158") (name "unconnected-(JTAG-Pad8)") (class "Default")
      (node (ref "JTAG") (pin "8") (pinfunction "8_8") (pintype "passive"))
    )
    (net (code "159") (name "unconnected-(MIC_OUT-PadRING)") (class "Default")
      (node (ref "MIC_OUT") (pin "RING") (pinfunction "RING_RING") (pintype "passive"))
    )
    (net (code "160") (name "unconnected-(MIC_OUT-PadRING_SWITCH)") (class "Default")
      (node (ref "MIC_OUT") (pin "RING_SWITCH") (pinfunction "RING_SWITCH_RING_SWITCH") (pintype "passive"))
    )
    (net (code "161") (name "unconnected-(MIC_OUT-PadTIP_SWITCH)") (class "Default")
      (node (ref "MIC_OUT") (pin "TIP_SWITCH") (pinfunction "TIP_SWITCH_TIP_SWITCH") (pintype "passive"))
    )
    (net (code "162") (name "unconnected-(PS2-Pad2)") (class "Default")
      (node (ref "PS2") (pin "2") (pinfunction "2_2") (pintype "passive"))
    )
    (net (code "163") (name "unconnected-(PS2-Pad6)") (class "Default")
      (node (ref "PS2") (pin "6") (pinfunction "6_6") (pintype "passive"))
    )
    (net (code "164") (name "unconnected-(S1-Pad1)") (class "Default")
      (node (ref "S1") (pin "1") (pinfunction "1_1") (pintype "bidirectional"))
    )
    (net (code "165") (name "unconnected-(SERIAL-Pad1)") (class "Default")
      (node (ref "SERIAL") (pin "1") (pinfunction "1_1") (pintype "passive"))
    )
    (net (code "166") (name "unconnected-(SERIAL-Pad4)") (class "Default")
      (node (ref "SERIAL") (pin "4") (pinfunction "4_4") (pintype "passive"))
    )
    (net (code "167") (name "unconnected-(SERIAL-Pad6)") (class "Default")
      (node (ref "SERIAL") (pin "6") (pinfunction "6_6") (pintype "passive"))
    )
    (net (code "168") (name "unconnected-(SERIAL-Pad9)") (class "Default")
      (node (ref "SERIAL") (pin "9") (pinfunction "9_9") (pintype "passive"))
    )
    (net (code "169") (name "unconnected-(TAPE_IN-PadRING)") (class "Default")
      (node (ref "TAPE_IN") (pin "RING") (pinfunction "RING_RING") (pintype "passive"))
    )
    (net (code "170") (name "unconnected-(TAPE_IN-PadRING_SWITCH)") (class "Default")
      (node (ref "TAPE_IN") (pin "RING_SWITCH") (pinfunction "RING_SWITCH_RING_SWITCH") (pintype "passive"))
    )
    (net (code "171") (name "unconnected-(TAPE_IN-PadTIP_SWITCH)") (class "Default")
      (node (ref "TAPE_IN") (pin "TIP_SWITCH") (pinfunction "TIP_SWITCH_TIP_SWITCH") (pintype "passive"))
    )
    (net (code "172") (name "unconnected-(TAPE_OUT-PadRING_SWITCH)") (class "Default")
      (node (ref "TAPE_OUT") (pin "RING_SWITCH") (pinfunction "RING_SWITCH_RING_SWITCH") (pintype "passive"))
    )
    (net (code "173") (name "unconnected-(TAPE_OUT-PadTIP_SWITCH)") (class "Default")
      (node (ref "TAPE_OUT") (pin "TIP_SWITCH") (pinfunction "TIP_SWITCH_TIP_SWITCH") (pintype "passive"))
    )
    (net (code "174") (name "unconnected-(U1-IO-Pad10)") (class "Default")
      (node (ref "U1") (pin "10") (pinfunction "IO_10") (pintype "bidirectional"))
    )
    (net (code "175") (name "unconnected-(U1-IO-Pad11)") (class "Default")
      (node (ref "U1") (pin "11") (pinfunction "IO_11") (pintype "bidirectional"))
    )
    (net (code "176") (name "unconnected-(U1-IO-Pad33)") (class "Default")
      (node (ref "U1") (pin "33") (pinfunction "IO_33") (pintype "bidirectional"))
    )
    (net (code "177") (name "unconnected-(U1-IO-Pad114)") (class "Default")
      (node (ref "U1") (pin "114") (pinfunction "IO_114") (pintype "bidirectional"))
    )
    (net (code "178") (name "unconnected-(U1-IO-Pad115)") (class "Default")
      (node (ref "U1") (pin "115") (pinfunction "IO_115") (pintype "bidirectional"))
    )
    (net (code "179") (name "unconnected-(U1-IO-Pad128)") (class "Default")
      (node (ref "U1") (pin "128") (pinfunction "IO_128") (pintype "bidirectional"))
    )
    (net (code "180") (name "unconnected-(U1-IO-Pad129)") (class "Default")
      (node (ref "U1") (pin "129") (pinfunction "IO_129") (pintype "bidirectional"))
    )
    (net (code "181") (name "unconnected-(U1-IO-Pad132)") (class "Default")
      (node (ref "U1") (pin "132") (pinfunction "IO_132") (pintype "bidirectional"))
    )
    (net (code "182") (name "unconnected-(U1-IO-Pad133)") (class "Default")
      (node (ref "U1") (pin "133") (pinfunction "IO_133") (pintype "bidirectional"))
    )
    (net (code "183") (name "unconnected-(U1-IO-Pad135)") (class "Default")
      (node (ref "U1") (pin "135") (pinfunction "IO_135") (pintype "bidirectional"))
    )
    (net (code "184") (name "unconnected-(U1-IO-Pad136)") (class "Default")
      (node (ref "U1") (pin "136") (pinfunction "IO_136") (pintype "bidirectional"))
    )
    (net (code "185") (name "unconnected-(U1-IO-Pad137)") (class "Default")
      (node (ref "U1") (pin "137") (pinfunction "IO_137") (pintype "bidirectional"))
    )
    (net (code "186") (name "unconnected-(U1-IO-Pad138)") (class "Default")
      (node (ref "U1") (pin "138") (pinfunction "IO_138") (pintype "bidirectional"))
    )
    (net (code "187") (name "unconnected-(U1-IO-Pad141)") (class "Default")
      (node (ref "U1") (pin "141") (pinfunction "IO_141") (pintype "bidirectional"))
    )
    (net (code "188") (name "unconnected-(U1-IO-Pad142)") (class "Default")
      (node (ref "U1") (pin "142") (pinfunction "IO_142") (pintype "bidirectional"))
    )
    (net (code "189") (name "unconnected-(VGA-Pad4)") (class "Default")
      (node (ref "VGA") (pin "4") (pinfunction "4_4") (pintype "passive"))
    )
    (net (code "190") (name "unconnected-(VGA-Pad9)") (class "Default")
      (node (ref "VGA") (pin "9") (pinfunction "9_9") (pintype "passive"))
    )
    (net (code "191") (name "unconnected-(VGA-Pad11)") (class "Default")
      (node (ref "VGA") (pin "11") (pinfunction "11_11") (pintype "passive"))
    )
    (net (code "192") (name "unconnected-(VGA-Pad12)") (class "Default")
      (node (ref "VGA") (pin "12") (pinfunction "12_12") (pintype "passive"))
    )
    (net (code "193") (name "unconnected-(VGA-Pad15)") (class "Default")
      (node (ref "VGA") (pin "15") (pinfunction "15_15") (pintype "passive"))
    )
  )
)
